# board.net
KiCad netlist of a schematic drawn in EAGLE
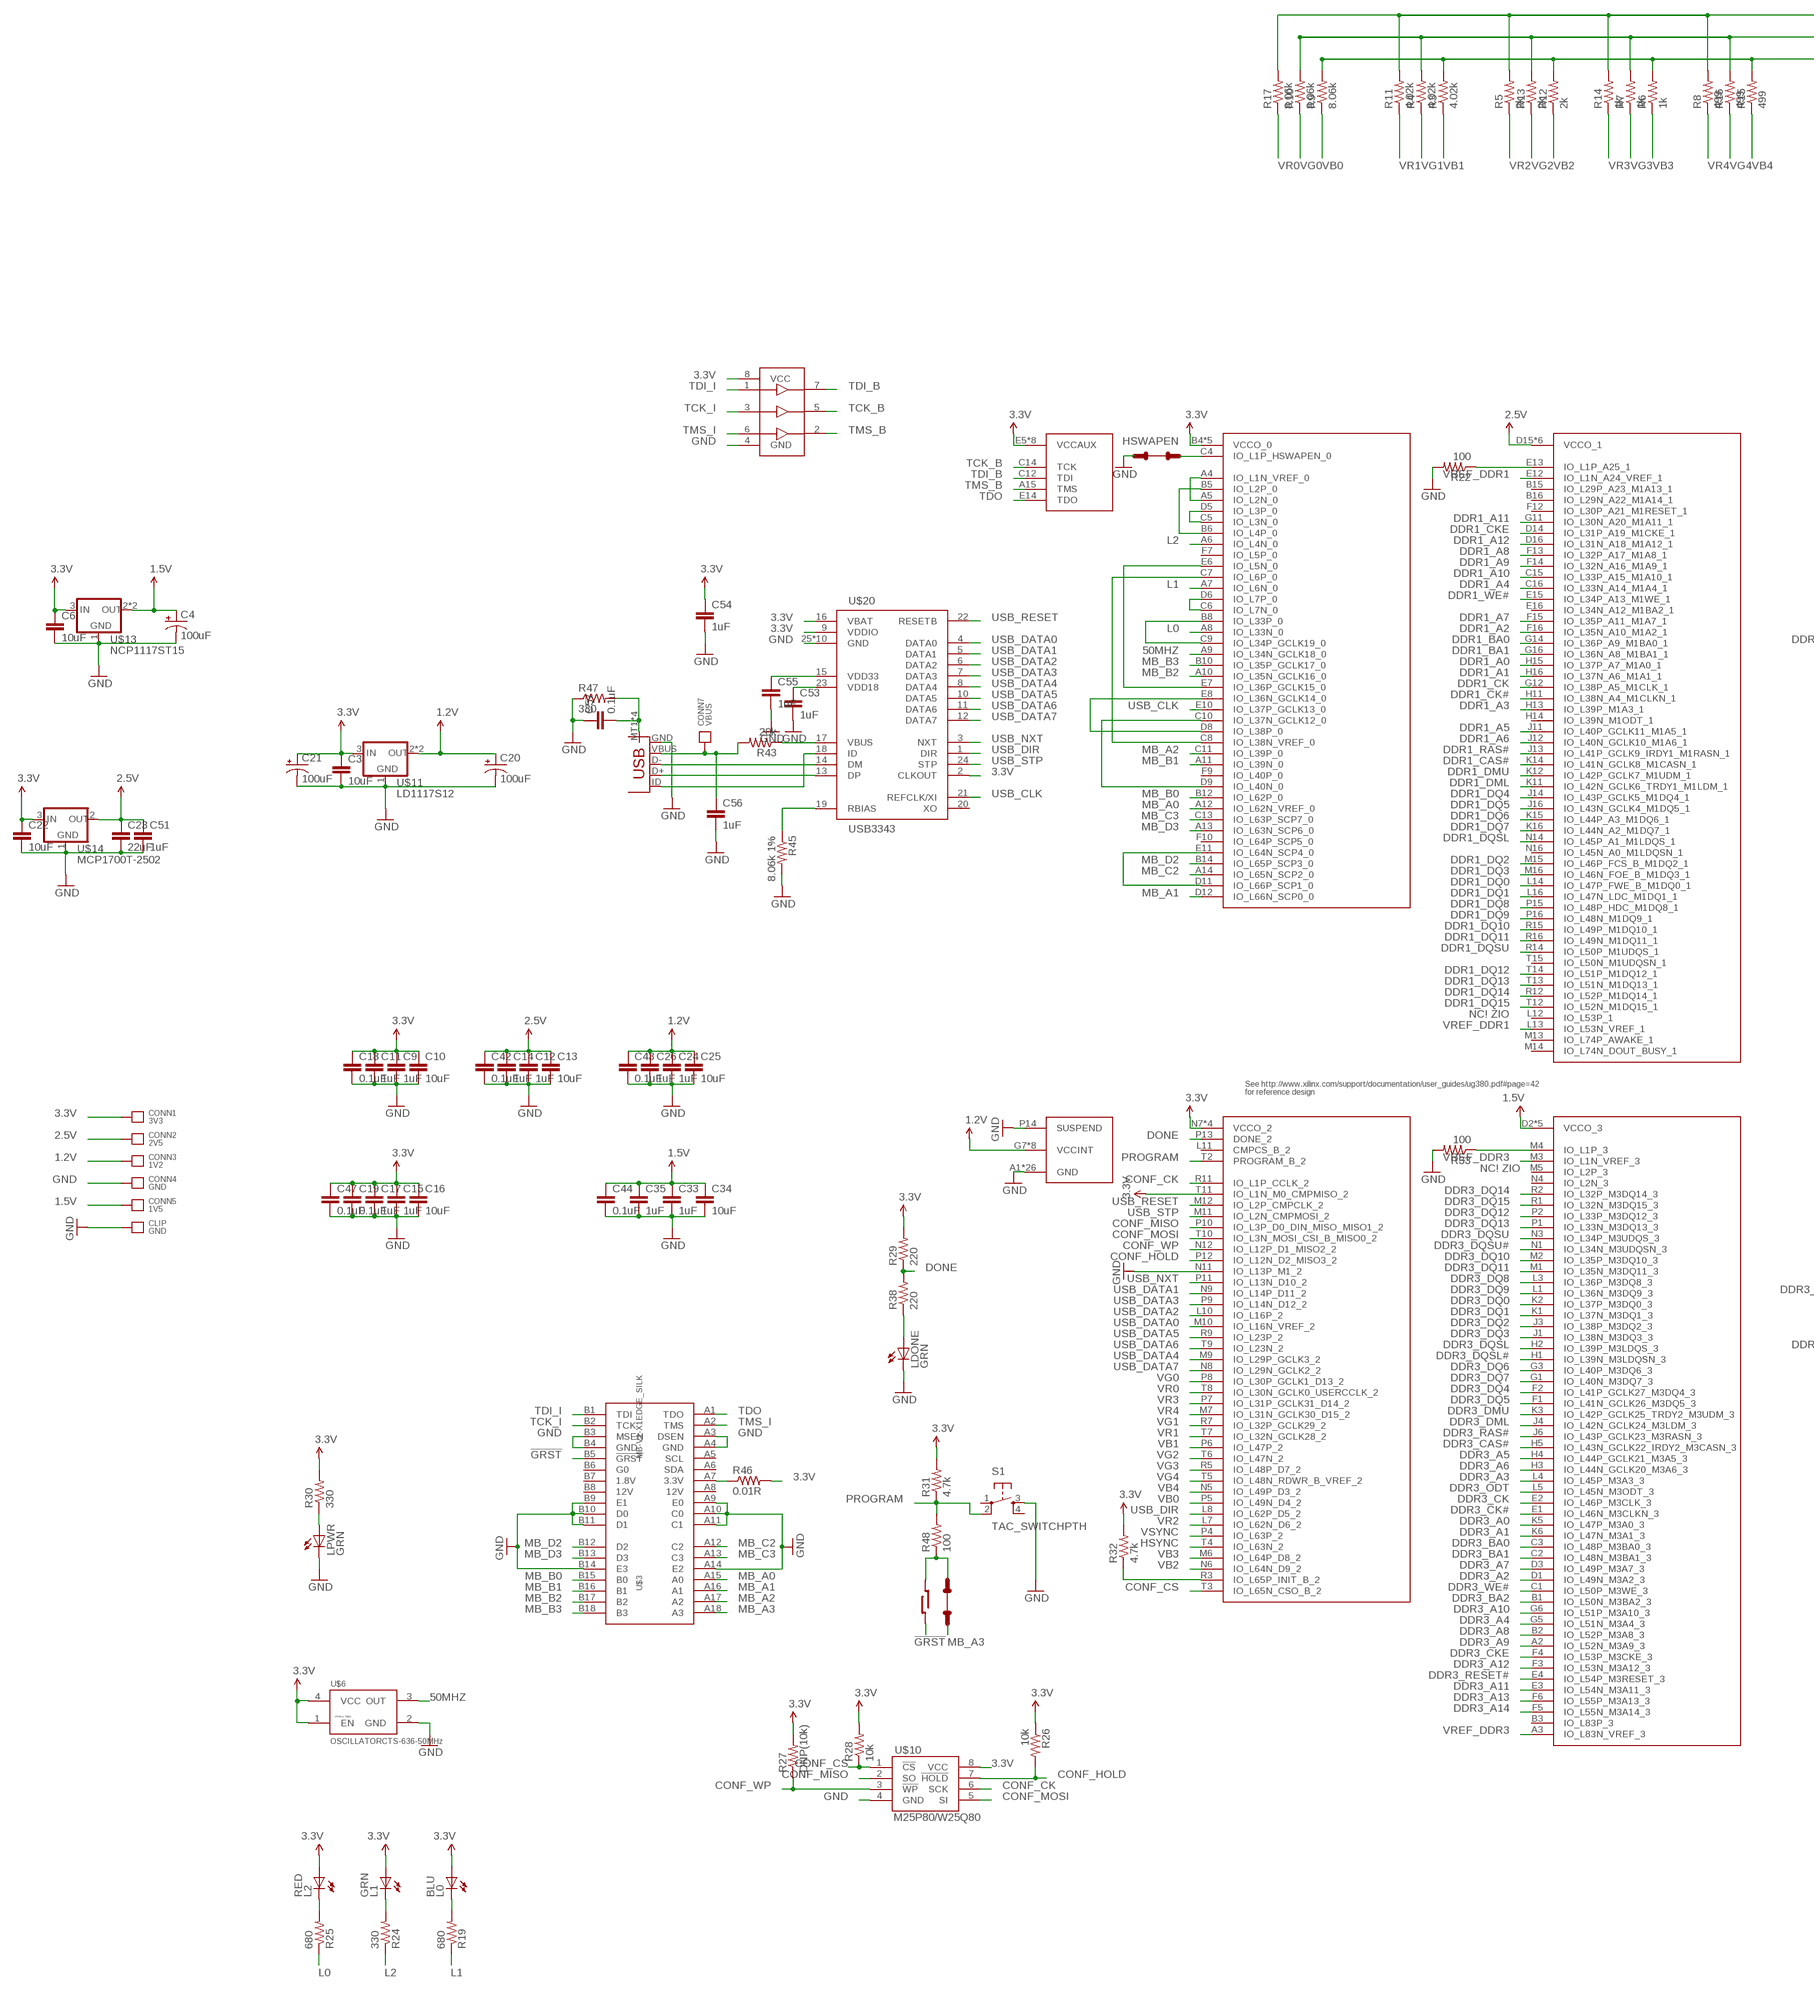
[diagram p0: schematic, sheet 1, part 1 of 2]
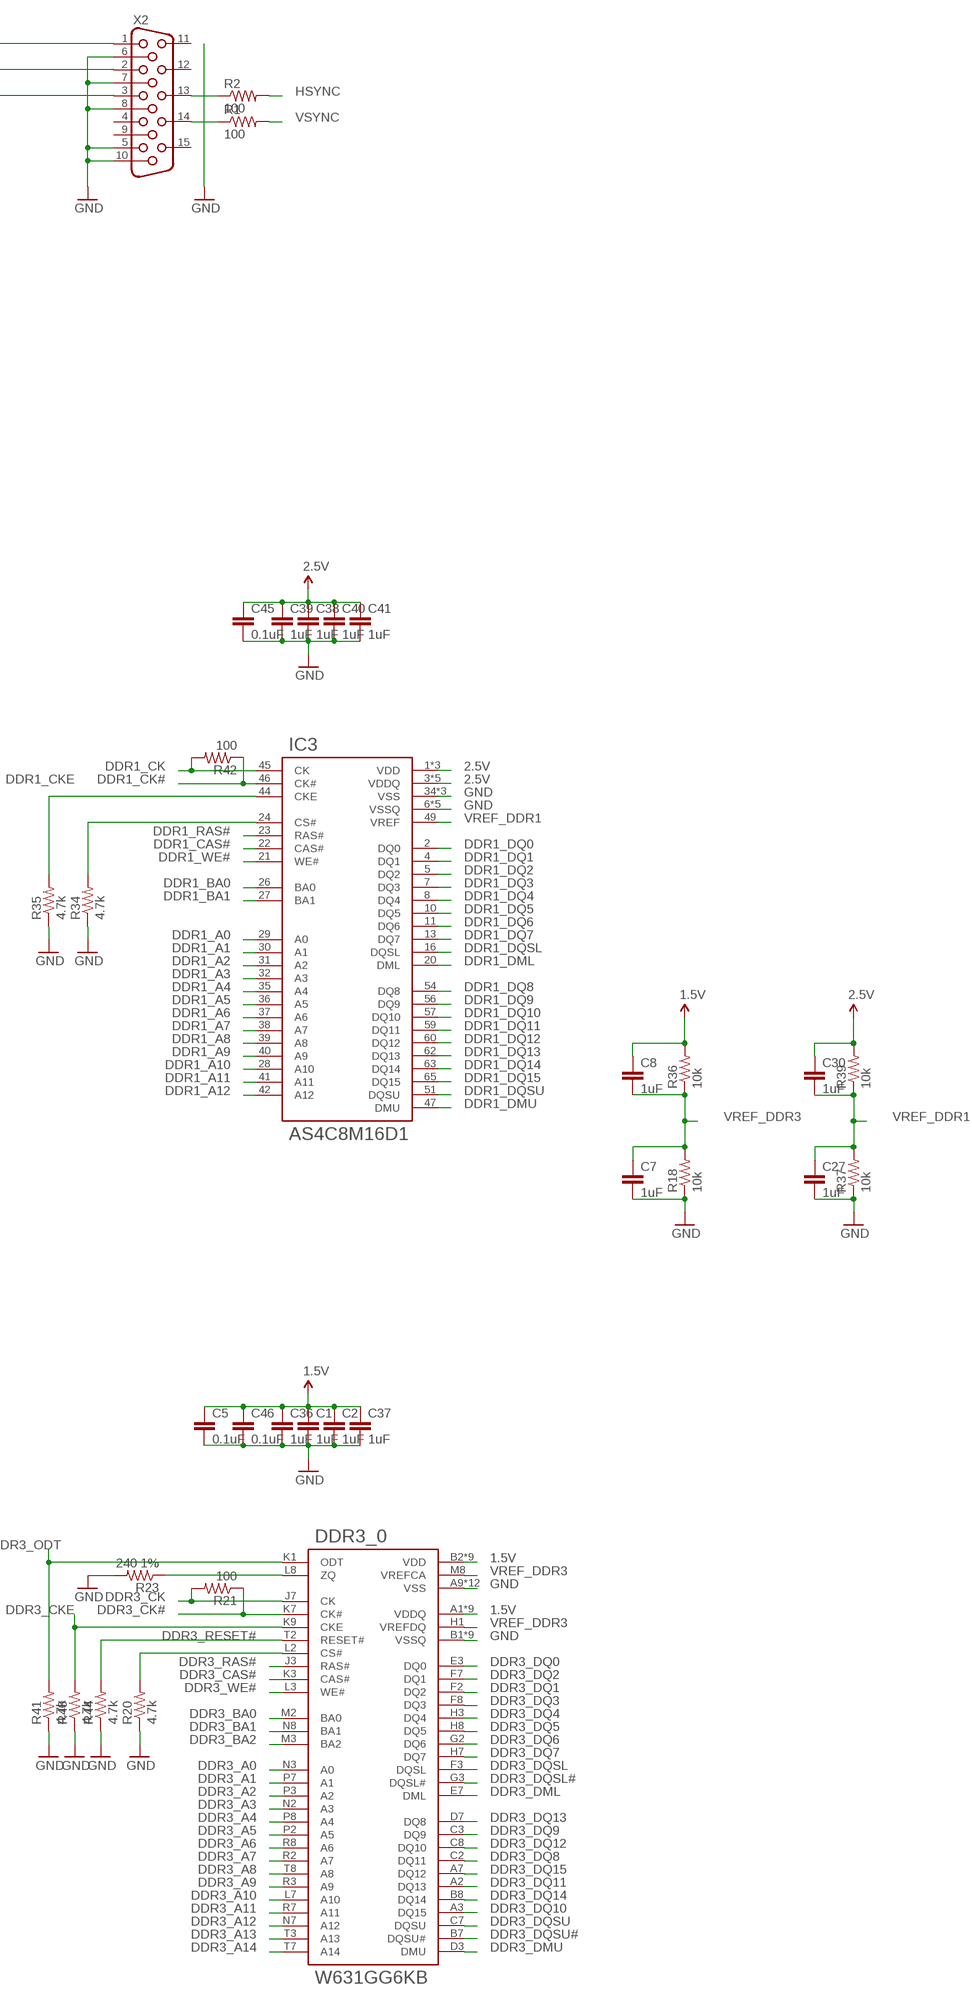
[diagram p1: schematic, sheet 1, part 2 of 2]

(export (version "E")
  (design (tool "Eeschema 10.0.6"))
  (components
    (comp (ref "C1")
      (value "1uF")
      (footprint "eagle-import:0402-CAP")
      (libsource (lib "eagle-import") (part "CAP0402-CAP"))
    )
    (comp (ref "C2")
      (value "1uF")
      (footprint "eagle-import:0402-CAP")
      (libsource (lib "eagle-import") (part "CAP0402-CAP"))
    )
    (comp (ref "C3")
      (value "10uF")
      (footprint "eagle-import:0603-CAP")
      (libsource (lib "eagle-import") (part "CAP0603"))
    )
    (comp (ref "C4")
      (value "100uF")
      (footprint "eagle-import:CAP-5-2")
      (libsource (lib "eagle-import") (part "CAP_POLPTH-5-2"))
    )
    (comp (ref "C5")
      (value "0.1uF")
      (footprint "eagle-import:C0201")
      (libsource (lib "eagle-import") (part "CAP0201"))
    )
    (comp (ref "C6")
      (value "10uF")
      (footprint "eagle-import:0603-CAP")
      (libsource (lib "eagle-import") (part "CAP0603"))
    )
    (comp (ref "C7")
      (value "1uF")
      (footprint "eagle-import:0402-CAP")
      (libsource (lib "eagle-import") (part "CAP0402-CAP"))
    )
    (comp (ref "C8")
      (value "1uF")
      (footprint "eagle-import:0402-CAP")
      (libsource (lib "eagle-import") (part "CAP0402-CAP"))
    )
    (comp (ref "C9")
      (value "1uF")
      (footprint "eagle-import:0402-CAP")
      (libsource (lib "eagle-import") (part "CAP0402-CAP"))
    )
    (comp (ref "C10")
      (value "10uF")
      (footprint "eagle-import:0603-CAP")
      (libsource (lib "eagle-import") (part "CAP0603"))
    )
    (comp (ref "C11")
      (value "1uF")
      (footprint "eagle-import:0402-CAP")
      (libsource (lib "eagle-import") (part "CAP0402-CAP"))
    )
    (comp (ref "C12")
      (value "1uF")
      (footprint "eagle-import:0402-CAP")
      (libsource (lib "eagle-import") (part "CAP0402-CAP"))
    )
    (comp (ref "C13")
      (value "10uF")
      (footprint "eagle-import:0603-CAP")
      (libsource (lib "eagle-import") (part "CAP0603"))
    )
    (comp (ref "C14")
      (value "1uF")
      (footprint "eagle-import:0402-CAP")
      (libsource (lib "eagle-import") (part "CAP0402-CAP"))
    )
    (comp (ref "C15")
      (value "1uF")
      (footprint "eagle-import:0402-CAP")
      (libsource (lib "eagle-import") (part "CAP0402-CAP"))
    )
    (comp (ref "C16")
      (value "10uF")
      (footprint "eagle-import:0603-CAP")
      (libsource (lib "eagle-import") (part "CAP0603"))
    )
    (comp (ref "C17")
      (value "1uF")
      (footprint "eagle-import:0402-CAP")
      (libsource (lib "eagle-import") (part "CAP0402-CAP"))
    )
    (comp (ref "C18")
      (value "0.1uF")
      (footprint "eagle-import:C0201")
      (libsource (lib "eagle-import") (part "CAP0201"))
    )
    (comp (ref "C19")
      (value "0.1uF")
      (footprint "eagle-import:C0201")
      (libsource (lib "eagle-import") (part "CAP0201"))
    )
    (comp (ref "C20")
      (value "100uF")
      (footprint "eagle-import:CAP-5-2")
      (libsource (lib "eagle-import") (part "CAP_POLPTH-5-2"))
    )
    (comp (ref "C21")
      (value "100uF")
      (footprint "eagle-import:CAP-5-2")
      (libsource (lib "eagle-import") (part "CAP_POLPTH-5-2"))
    )
    (comp (ref "C22")
      (value "10uF")
      (footprint "eagle-import:0603-CAP")
      (libsource (lib "eagle-import") (part "CAP0603"))
    )
    (comp (ref "C23")
      (value "22uF")
      (footprint "eagle-import:0805")
      (libsource (lib "eagle-import") (part "CAP0805"))
    )
    (comp (ref "C24")
      (value "1uF")
      (footprint "eagle-import:0402-CAP")
      (libsource (lib "eagle-import") (part "CAP0402-CAP"))
    )
    (comp (ref "C25")
      (value "10uF")
      (footprint "eagle-import:0603-CAP")
      (libsource (lib "eagle-import") (part "CAP0603"))
    )
    (comp (ref "C26")
      (value "1uF")
      (footprint "eagle-import:0402-CAP")
      (libsource (lib "eagle-import") (part "CAP0402-CAP"))
    )
    (comp (ref "C27")
      (value "1uF")
      (footprint "eagle-import:0402-CAP")
      (libsource (lib "eagle-import") (part "CAP0402-CAP"))
    )
    (comp (ref "C30")
      (value "1uF")
      (footprint "eagle-import:0402-CAP")
      (libsource (lib "eagle-import") (part "CAP0402-CAP"))
    )
    (comp (ref "C33")
      (value "1uF")
      (footprint "eagle-import:0402-CAP")
      (libsource (lib "eagle-import") (part "CAP0402-CAP"))
    )
    (comp (ref "C34")
      (value "10uF")
      (footprint "eagle-import:0603-CAP")
      (libsource (lib "eagle-import") (part "CAP0603"))
    )
    (comp (ref "C35")
      (value "1uF")
      (footprint "eagle-import:0402-CAP")
      (libsource (lib "eagle-import") (part "CAP0402-CAP"))
    )
    (comp (ref "C36")
      (value "1uF")
      (footprint "eagle-import:0402-CAP")
      (libsource (lib "eagle-import") (part "CAP0402-CAP"))
    )
    (comp (ref "C37")
      (value "1uF")
      (footprint "eagle-import:0402-CAP")
      (libsource (lib "eagle-import") (part "CAP0402-CAP"))
    )
    (comp (ref "C38")
      (value "1uF")
      (footprint "eagle-import:0402-CAP")
      (libsource (lib "eagle-import") (part "CAP0402-CAP"))
    )
    (comp (ref "C39")
      (value "1uF")
      (footprint "eagle-import:0402-CAP")
      (libsource (lib "eagle-import") (part "CAP0402-CAP"))
    )
    (comp (ref "C40")
      (value "1uF")
      (footprint "eagle-import:0402-CAP")
      (libsource (lib "eagle-import") (part "CAP0402-CAP"))
    )
    (comp (ref "C41")
      (value "1uF")
      (footprint "eagle-import:0402-CAP")
      (libsource (lib "eagle-import") (part "CAP0402-CAP"))
    )
    (comp (ref "C42")
      (value "0.1uF")
      (footprint "eagle-import:C0201")
      (libsource (lib "eagle-import") (part "CAP0201"))
    )
    (comp (ref "C43")
      (value "0.1uF")
      (footprint "eagle-import:C0201")
      (libsource (lib "eagle-import") (part "CAP0201"))
    )
    (comp (ref "C44")
      (value "0.1uF")
      (footprint "eagle-import:C0201")
      (libsource (lib "eagle-import") (part "CAP0201"))
    )
    (comp (ref "C45")
      (value "0.1uF")
      (footprint "eagle-import:C0201")
      (libsource (lib "eagle-import") (part "CAP0201"))
    )
    (comp (ref "C46")
      (value "0.1uF")
      (footprint "eagle-import:C0201")
      (libsource (lib "eagle-import") (part "CAP0201"))
    )
    (comp (ref "C47")
      (value "0.1uF")
      (footprint "eagle-import:C0201")
      (libsource (lib "eagle-import") (part "CAP0201"))
    )
    (comp (ref "C51")
      (value "1uF")
      (footprint "eagle-import:0402-CAP")
      (libsource (lib "eagle-import") (part "CAP0402-CAP"))
    )
    (comp (ref "C53")
      (value "1uF")
      (footprint "eagle-import:0402-CAP")
      (libsource (lib "eagle-import") (part "CAP0402-CAP"))
    )
    (comp (ref "C54")
      (value "1uF")
      (footprint "eagle-import:0402-CAP")
      (libsource (lib "eagle-import") (part "CAP0402-CAP"))
    )
    (comp (ref "C55")
      (value "1uF")
      (footprint "eagle-import:0402-CAP")
      (libsource (lib "eagle-import") (part "CAP0402-CAP"))
    )
    (comp (ref "C56")
      (value "1uF")
      (footprint "eagle-import:0402-CAP")
      (libsource (lib "eagle-import") (part "CAP0402-CAP"))
    )
    (comp (ref "C57")
      (value "0.1uF")
      (footprint "eagle-import:0402-CAP")
      (libsource (lib "eagle-import") (part "CAP0402-CAP"))
    )
    (comp (ref "CLIP")
      (value "GND")
      (footprint "eagle-import:CLIP-AREA")
      (libsource (lib "eagle-import") (part "CONNECTORCLIP"))
    )
    (comp (ref "CONN1")
      (value "3V3")
      (footprint "eagle-import:HOLE_22AWG")
      (libsource (lib "eagle-import") (part "CONNECTOR22AWG"))
    )
    (comp (ref "CONN2")
      (value "2V5")
      (footprint "eagle-import:HOLE_22AWG")
      (libsource (lib "eagle-import") (part "CONNECTOR22AWG"))
    )
    (comp (ref "CONN3")
      (value "1V2")
      (footprint "eagle-import:HOLE_22AWG")
      (libsource (lib "eagle-import") (part "CONNECTOR22AWG"))
    )
    (comp (ref "CONN4")
      (value "GND")
      (footprint "eagle-import:HOLE_22AWG")
      (libsource (lib "eagle-import") (part "CONNECTOR22AWG"))
    )
    (comp (ref "CONN5")
      (value "1V5")
      (footprint "eagle-import:HOLE_22AWG")
      (libsource (lib "eagle-import") (part "CONNECTOR22AWG"))
    )
    (comp (ref "CONN7")
      (value "VBUS")
      (footprint "eagle-import:HOLE_22AWG")
      (libsource (lib "eagle-import") (part "CONNECTOR22AWG"))
    )
    (comp (ref "DDR3_0")
      (value "W631GG6KB")
      (footprint "eagle-import:BGA96")
      (libsource (lib "eagle-import") (part "DDR3X16"))
    )
    (comp (ref "IC1")
      (value "XC6S{9,16,25}LX-FT256")
      (footprint "eagle-import:XILINX_FT256")
      (libsource (lib "eagle-import") (part "XC6S{9,16,25}LX-FT256"))
    )
    (comp (ref "IC2")
      (value "74LVC3G34")
      (footprint "eagle-import:TSSOP8")
      (libsource (lib "eagle-import") (part "74X3G34"))
    )
    (comp (ref "IC3")
      (value "AS4C8M16D1")
      (footprint "eagle-import:TSOP66-400")
      (libsource (lib "eagle-import") (part "DDR1X16"))
    )
    (comp (ref "JP1")
      (value "USBMICRO")
      (footprint "eagle-import:USB-MICRO")
      (libsource (lib "eagle-import") (part "USBMICRO"))
    )
    (comp (ref "L0")
      (value "BLU")
      (footprint "eagle-import:0603_LED")
      (libsource (lib "eagle-import") (part "LED0603"))
    )
    (comp (ref "L1")
      (value "GRN")
      (footprint "eagle-import:0603_LED")
      (libsource (lib "eagle-import") (part "LED0603"))
    )
    (comp (ref "L2")
      (value "RED")
      (footprint "eagle-import:0603_LED")
      (libsource (lib "eagle-import") (part "LED0603"))
    )
    (comp (ref "LDONE")
      (value "GRN")
      (footprint "eagle-import:0603_LED")
      (libsource (lib "eagle-import") (part "LED0603"))
    )
    (comp (ref "LPWR")
      (value "GRN")
      (footprint "eagle-import:0603_LED")
      (libsource (lib "eagle-import") (part "LED0603"))
    )
    (comp (ref "R1")
      (value "100")
      (footprint "eagle-import:0603-RES")
      (libsource (lib "eagle-import") (part "RESISTOR0603"))
    )
    (comp (ref "R2")
      (value "100")
      (footprint "eagle-import:0603-RES")
      (libsource (lib "eagle-import") (part "RESISTOR0603"))
    )
    (comp (ref "R3")
      (value "4.02k")
      (footprint "eagle-import:0603-RES")
      (libsource (lib "eagle-import") (part "RESISTOR0603"))
    )
    (comp (ref "R4")
      (value "4.02k")
      (footprint "eagle-import:0603-RES")
      (libsource (lib "eagle-import") (part "RESISTOR0603"))
    )
    (comp (ref "R5")
      (value "2k")
      (footprint "eagle-import:0603-RES")
      (libsource (lib "eagle-import") (part "RESISTOR0603"))
    )
    (comp (ref "R6")
      (value "1k")
      (footprint "eagle-import:0603-RES")
      (libsource (lib "eagle-import") (part "RESISTOR0603"))
    )
    (comp (ref "R7")
      (value "1k")
      (footprint "eagle-import:0603-RES")
      (libsource (lib "eagle-import") (part "RESISTOR0603"))
    )
    (comp (ref "R8")
      (value "499")
      (footprint "eagle-import:0603-RES")
      (libsource (lib "eagle-import") (part "RESISTOR0603"))
    )
    (comp (ref "R9")
      (value "8.06k")
      (footprint "eagle-import:0603-RES")
      (libsource (lib "eagle-import") (part "RESISTOR0603"))
    )
    (comp (ref "R10")
      (value "8.06k")
      (footprint "eagle-import:0603-RES")
      (libsource (lib "eagle-import") (part "RESISTOR0603"))
    )
    (comp (ref "R11")
      (value "4.02k")
      (footprint "eagle-import:0603-RES")
      (libsource (lib "eagle-import") (part "RESISTOR0603"))
    )
    (comp (ref "R12")
      (value "2k")
      (footprint "eagle-import:0603-RES")
      (libsource (lib "eagle-import") (part "RESISTOR0603"))
    )
    (comp (ref "R13")
      (value "2k")
      (footprint "eagle-import:0603-RES")
      (libsource (lib "eagle-import") (part "RESISTOR0603"))
    )
    (comp (ref "R14")
      (value "1k")
      (footprint "eagle-import:0603-RES")
      (libsource (lib "eagle-import") (part "RESISTOR0603"))
    )
    (comp (ref "R15")
      (value "499")
      (footprint "eagle-import:0603-RES")
      (libsource (lib "eagle-import") (part "RESISTOR0603"))
    )
    (comp (ref "R16")
      (value "499")
      (footprint "eagle-import:0603-RES")
      (libsource (lib "eagle-import") (part "RESISTOR0603"))
    )
    (comp (ref "R17")
      (value "8.06k")
      (footprint "eagle-import:0603-RES")
      (libsource (lib "eagle-import") (part "RESISTOR0603"))
    )
    (comp (ref "R18")
      (value "10k")
      (footprint "eagle-import:0603-RES")
      (libsource (lib "eagle-import") (part "RESISTOR0603"))
    )
    (comp (ref "R19")
      (value "680")
      (footprint "eagle-import:0603-RES")
      (libsource (lib "eagle-import") (part "RESISTOR0603"))
    )
    (comp (ref "R20")
      (value "4.7k")
      (footprint "eagle-import:0402-RES")
      (libsource (lib "eagle-import") (part "RESISTOR0402"))
    )
    (comp (ref "R21")
      (value "100")
      (footprint "eagle-import:0603-RES")
      (libsource (lib "eagle-import") (part "RESISTOR0603"))
    )
    (comp (ref "R22")
      (value "100")
      (footprint "eagle-import:0603-RES")
      (libsource (lib "eagle-import") (part "RESISTOR0603"))
    )
    (comp (ref "R23")
      (value "240 1%")
      (footprint "eagle-import:0402-RES")
      (libsource (lib "eagle-import") (part "RESISTOR0402"))
    )
    (comp (ref "R24")
      (value "330")
      (footprint "eagle-import:0603-RES")
      (libsource (lib "eagle-import") (part "RESISTOR0603"))
    )
    (comp (ref "R25")
      (value "680")
      (footprint "eagle-import:0603-RES")
      (libsource (lib "eagle-import") (part "RESISTOR0603"))
    )
    (comp (ref "R26")
      (value "10k")
      (footprint "eagle-import:0402-RES")
      (libsource (lib "eagle-import") (part "RESISTOR0402"))
    )
    (comp (ref "R27")
      (value "DNP(10k)")
      (footprint "eagle-import:0402-RES")
      (libsource (lib "eagle-import") (part "RESISTOR0402"))
    )
    (comp (ref "R28")
      (value "10k")
      (footprint "eagle-import:0603-RES")
      (libsource (lib "eagle-import") (part "RESISTOR0603"))
    )
    (comp (ref "R29")
      (value "220")
      (footprint "eagle-import:0603-RES")
      (libsource (lib "eagle-import") (part "RESISTOR0603"))
    )
    (comp (ref "R30")
      (value "330")
      (footprint "eagle-import:0603-RES")
      (libsource (lib "eagle-import") (part "RESISTOR0603"))
    )
    (comp (ref "R31")
      (value "4.7k")
      (footprint "eagle-import:0603-RES")
      (libsource (lib "eagle-import") (part "RESISTOR0603"))
    )
    (comp (ref "R32")
      (value "4.7k")
      (footprint "eagle-import:0603-RES")
      (libsource (lib "eagle-import") (part "RESISTOR0603"))
    )
    (comp (ref "R33")
      (value "100")
      (footprint "eagle-import:0603-RES")
      (libsource (lib "eagle-import") (part "RESISTOR0603"))
    )
    (comp (ref "R34")
      (value "4.7k")
      (footprint "eagle-import:0402-RES")
      (libsource (lib "eagle-import") (part "RESISTOR0402"))
    )
    (comp (ref "R35")
      (value "4.7k")
      (footprint "eagle-import:0402-RES")
      (libsource (lib "eagle-import") (part "RESISTOR0402"))
    )
    (comp (ref "R36")
      (value "10k")
      (footprint "eagle-import:0603-RES")
      (libsource (lib "eagle-import") (part "RESISTOR0603"))
    )
    (comp (ref "R37")
      (value "10k")
      (footprint "eagle-import:0603-RES")
      (libsource (lib "eagle-import") (part "RESISTOR0603"))
    )
    (comp (ref "R38")
      (value "220")
      (footprint "eagle-import:0603-RES")
      (libsource (lib "eagle-import") (part "RESISTOR0603"))
    )
    (comp (ref "R39")
      (value "10k")
      (footprint "eagle-import:0603-RES")
      (libsource (lib "eagle-import") (part "RESISTOR0603"))
    )
    (comp (ref "R40")
      (value "4.7k")
      (footprint "eagle-import:0402-RES")
      (libsource (lib "eagle-import") (part "RESISTOR0402"))
    )
    (comp (ref "R41")
      (value "4.7k")
      (footprint "eagle-import:0402-RES")
      (libsource (lib "eagle-import") (part "RESISTOR0402"))
    )
    (comp (ref "R42")
      (value "100")
      (footprint "eagle-import:0402-RES")
      (libsource (lib "eagle-import") (part "RESISTOR0402"))
    )
    (comp (ref "R43")
      (value "20k")
      (footprint "eagle-import:0402-RES")
      (libsource (lib "eagle-import") (part "RESISTOR0402"))
    )
    (comp (ref "R44")
      (value "4.7k")
      (footprint "eagle-import:0402-RES")
      (libsource (lib "eagle-import") (part "RESISTOR0402"))
    )
    (comp (ref "R45")
      (value "8.06k 1%")
      (footprint "eagle-import:0603-RES")
      (libsource (lib "eagle-import") (part "RESISTOR0603"))
    )
    (comp (ref "R46")
      (value "0.01R")
      (footprint "eagle-import:0603-RES")
      (libsource (lib "eagle-import") (part "RESISTOR0603"))
    )
    (comp (ref "R47")
      (value "330")
      (footprint "eagle-import:0603-RES")
      (libsource (lib "eagle-import") (part "RESISTOR0603"))
    )
    (comp (ref "R48")
      (value "100")
      (footprint "eagle-import:0603-RES")
      (libsource (lib "eagle-import") (part "RESISTOR0603"))
    )
    (comp (ref "S1")
      (value "TAC_SWITCHPTH")
      (footprint "eagle-import:TACTILE-PTH")
      (libsource (lib "eagle-import") (part "TAC_SWITCHPTH"))
    )
    (comp (ref "SB1")
      (value "SOLDER-BRIDGEOPEN")
      (footprint "eagle-import:SOLDER-BRIDGE-OPEN")
      (libsource (lib "eagle-import") (part "SOLDER-BRIDGEOPEN"))
    )
    (comp (ref "SB2")
      (value "TRACE-CUT")
      (footprint "eagle-import:TRACE-CUT")
      (libsource (lib "eagle-import") (part "TRACE-CUT"))
    )
    (comp (ref "SB5")
      (value "TRACE-CUT")
      (footprint "eagle-import:TRACE-CUT")
      (libsource (lib "eagle-import") (part "TRACE-CUT"))
    )
    (comp (ref "U$3")
      (value "MB-V1-X1EDGE_SILK")
      (footprint "eagle-import:MB-V1-X1-EDGE")
      (libsource (lib "eagle-import") (part "MB-V1-X1EDGE_SILK"))
    )
    (comp (ref "U$6")
      (value "OSCILLATORCTS-636-50MHz")
      (footprint "eagle-import:CTS-636")
      (libsource (lib "eagle-import") (part "OSCILLATORCTS-636"))
    )
    (comp (ref "U$10")
      (value "M25P80/W25Q80")
      (footprint "eagle-import:SO08")
      (libsource (lib "eagle-import") (part "S25FL"))
    )
    (comp (ref "U$11")
      (value "LD1117S12")
      (footprint "eagle-import:SOT223")
      (libsource (lib "eagle-import") (part "VREGSOT223"))
    )
    (comp (ref "U$13")
      (value "NCP1117ST15")
      (footprint "eagle-import:SOT223")
      (libsource (lib "eagle-import") (part "VREGSOT223"))
    )
    (comp (ref "U$14")
      (value "MCP1700T-2502")
      (footprint "eagle-import:SOT23-3")
      (libsource (lib "eagle-import") (part "VREGSOT23-3"))
    )
    (comp (ref "U$20")
      (value "USB3343")
      (footprint "eagle-import:QFN24")
      (libsource (lib "eagle-import") (part "USB3343"))
    )
    (comp (ref "X2")
      (value "HF15H")
      (footprint "eagle-import:HDF15H")
      (libsource (lib "eagle-import") (part "HF15H"))
    )
  )
  (nets
    (net (code "1") (name "/50MHZ") (class "Default")
      (node (ref "IC1") (pin "A9") (pinfunction "IO_L34N_GCLK18_0_A9") (pintype "bidirectional"))
      (node (ref "U$6") (pin "3") (pinfunction "OUT_3") (pintype "bidirectional"))
    )
    (net (code "2") (name "/CONF_CK") (class "Default")
      (node (ref "IC1") (pin "R11") (pinfunction "IO_L1P_CCLK_2_R11") (pintype "bidirectional"))
      (node (ref "U$10") (pin "6") (pinfunction "SCK_6") (pintype "bidirectional"))
    )
    (net (code "3") (name "/CONF_CS") (class "Default")
      (node (ref "IC1") (pin "T3") (pinfunction "IO_L65N_CSO_B_2_T3") (pintype "bidirectional"))
      (node (ref "R28") (pin "1") (pinfunction "1_1") (pintype "passive"))
      (node (ref "U$10") (pin "1") (pinfunction "~{CS}_1") (pintype "bidirectional"))
    )
    (net (code "4") (name "/CONF_HOLD") (class "Default")
      (node (ref "IC1") (pin "P12") (pinfunction "IO_L12N_D2_MISO3_2_P12") (pintype "bidirectional"))
      (node (ref "R26") (pin "2") (pinfunction "2_2") (pintype "passive"))
      (node (ref "U$10") (pin "7") (pinfunction "~{HOLD}_7") (pintype "bidirectional"))
    )
    (net (code "5") (name "/CONF_MISO") (class "Default")
      (node (ref "IC1") (pin "P10") (pinfunction "IO_L3P_D0_DIN_MISO_MISO1_2_P10") (pintype "bidirectional"))
      (node (ref "U$10") (pin "2") (pinfunction "SO_2") (pintype "bidirectional"))
    )
    (net (code "6") (name "/CONF_MOSI") (class "Default")
      (node (ref "IC1") (pin "T10") (pinfunction "IO_L3N_MOSI_CSI_B_MISO0_2_T10") (pintype "bidirectional"))
      (node (ref "U$10") (pin "5") (pinfunction "SI_5") (pintype "bidirectional"))
    )
    (net (code "7") (name "/CONF_WP") (class "Default")
      (node (ref "IC1") (pin "N12") (pinfunction "IO_L12P_D1_MISO2_2_N12") (pintype "bidirectional"))
      (node (ref "R27") (pin "1") (pinfunction "1_1") (pintype "passive"))
      (node (ref "U$10") (pin "3") (pinfunction "~{WP}_3") (pintype "bidirectional"))
    )
    (net (code "8") (name "/DDR1_A0") (class "Default")
      (node (ref "IC1") (pin "H15") (pinfunction "IO_L37P_A7_M1A0_1_H15") (pintype "bidirectional"))
      (node (ref "IC3") (pin "29") (pinfunction "A0_29") (pintype "input"))
    )
    (net (code "9") (name "/DDR1_A1") (class "Default")
      (node (ref "IC1") (pin "H16") (pinfunction "IO_L37N_A6_M1A1_1_H16") (pintype "bidirectional"))
      (node (ref "IC3") (pin "30") (pinfunction "A1_30") (pintype "input"))
    )
    (net (code "10") (name "/DDR1_A2") (class "Default")
      (node (ref "IC1") (pin "F16") (pinfunction "IO_L35N_A10_M1A2_1_F16") (pintype "bidirectional"))
      (node (ref "IC3") (pin "31") (pinfunction "A2_31") (pintype "input"))
    )
    (net (code "11") (name "/DDR1_A3") (class "Default")
      (node (ref "IC1") (pin "H13") (pinfunction "IO_L39P_M1A3_1_H13") (pintype "bidirectional"))
      (node (ref "IC3") (pin "32") (pinfunction "A3_32") (pintype "input"))
    )
    (net (code "12") (name "/DDR1_A4") (class "Default")
      (node (ref "IC1") (pin "C16") (pinfunction "IO_L33N_A14_M1A4_1_C16") (pintype "bidirectional"))
      (node (ref "IC3") (pin "35") (pinfunction "A4_35") (pintype "input"))
    )
    (net (code "13") (name "/DDR1_A5") (class "Default")
      (node (ref "IC1") (pin "J11") (pinfunction "IO_L40P_GCLK11_M1A5_1_J11") (pintype "bidirectional"))
      (node (ref "IC3") (pin "36") (pinfunction "A5_36") (pintype "input"))
    )
    (net (code "14") (name "/DDR1_A6") (class "Default")
      (node (ref "IC1") (pin "J12") (pinfunction "IO_L40N_GCLK10_M1A6_1_J12") (pintype "bidirectional"))
      (node (ref "IC3") (pin "37") (pinfunction "A6_37") (pintype "input"))
    )
    (net (code "15") (name "/DDR1_A7") (class "Default")
      (node (ref "IC1") (pin "F15") (pinfunction "IO_L35P_A11_M1A7_1_F15") (pintype "bidirectional"))
      (node (ref "IC3") (pin "38") (pinfunction "A7_38") (pintype "input"))
    )
    (net (code "16") (name "/DDR1_A8") (class "Default")
      (node (ref "IC1") (pin "F13") (pinfunction "IO_L32P_A17_M1A8_1_F13") (pintype "bidirectional"))
      (node (ref "IC3") (pin "39") (pinfunction "A8_39") (pintype "input"))
    )
    (net (code "17") (name "/DDR1_A9") (class "Default")
      (node (ref "IC1") (pin "F14") (pinfunction "IO_L32N_A16_M1A9_1_F14") (pintype "bidirectional"))
      (node (ref "IC3") (pin "40") (pinfunction "A9_40") (pintype "input"))
    )
    (net (code "18") (name "/DDR1_A10") (class "Default")
      (node (ref "IC1") (pin "C15") (pinfunction "IO_L33P_A15_M1A10_1_C15") (pintype "bidirectional"))
      (node (ref "IC3") (pin "28") (pinfunction "A10_28") (pintype "input"))
    )
    (net (code "19") (name "/DDR1_A11") (class "Default")
      (node (ref "IC1") (pin "G11") (pinfunction "IO_L30N_A20_M1A11_1_G11") (pintype "bidirectional"))
      (node (ref "IC3") (pin "41") (pinfunction "A11_41") (pintype "input"))
    )
    (net (code "20") (name "/DDR1_A12") (class "Default")
      (node (ref "IC1") (pin "D16") (pinfunction "IO_L31N_A18_M1A12_1_D16") (pintype "bidirectional"))
      (node (ref "IC3") (pin "42") (pinfunction "A12_42") (pintype "input"))
    )
    (net (code "21") (name "/DDR1_BA0") (class "Default")
      (node (ref "IC1") (pin "G14") (pinfunction "IO_L36P_A9_M1BA0_1_G14") (pintype "bidirectional"))
      (node (ref "IC3") (pin "26") (pinfunction "BA0_26") (pintype "input"))
    )
    (net (code "22") (name "/DDR1_BA1") (class "Default")
      (node (ref "IC1") (pin "G16") (pinfunction "IO_L36N_A8_M1BA1_1_G16") (pintype "bidirectional"))
      (node (ref "IC3") (pin "27") (pinfunction "BA1_27") (pintype "input"))
    )
    (net (code "23") (name "/DDR1_CAS#") (class "Default")
      (node (ref "IC1") (pin "K14") (pinfunction "IO_L41N_GCLK8_M1CASN_1_K14") (pintype "bidirectional"))
      (node (ref "IC3") (pin "22") (pinfunction "CAS#_22") (pintype "input"))
    )
    (net (code "24") (name "/DDR1_CK") (class "Default")
      (node (ref "IC1") (pin "G12") (pinfunction "IO_L38P_A5_M1CLK_1_G12") (pintype "bidirectional"))
      (node (ref "IC3") (pin "45") (pinfunction "CK_45") (pintype "input"))
      (node (ref "R42") (pin "2") (pinfunction "2_2") (pintype "passive"))
    )
    (net (code "25") (name "/DDR1_CK#") (class "Default")
      (node (ref "IC1") (pin "H11") (pinfunction "IO_L38N_A4_M1CLKN_1_H11") (pintype "bidirectional"))
      (node (ref "IC3") (pin "46") (pinfunction "CK#_46") (pintype "input"))
      (node (ref "R42") (pin "1") (pinfunction "1_1") (pintype "passive"))
    )
    (net (code "26") (name "/DDR1_CKE") (class "Default")
      (node (ref "IC1") (pin "D14") (pinfunction "IO_L31P_A19_M1CKE_1_D14") (pintype "bidirectional"))
      (node (ref "IC3") (pin "44") (pinfunction "CKE_44") (pintype "input"))
      (node (ref "R35") (pin "2") (pinfunction "2_2") (pintype "passive"))
    )
    (net (code "27") (name "/DDR1_DML") (class "Default")
      (node (ref "IC1") (pin "K11") (pinfunction "IO_L42N_GCLK6_TRDY1_M1LDM_1_K11") (pintype "bidirectional"))
      (node (ref "IC3") (pin "20") (pinfunction "DML_20") (pintype "input"))
    )
    (net (code "28") (name "/DDR1_DMU") (class "Default")
      (node (ref "IC1") (pin "K12") (pinfunction "IO_L42P_GCLK7_M1UDM_1_K12") (pintype "bidirectional"))
      (node (ref "IC3") (pin "47") (pinfunction "DMU_47") (pintype "input"))
    )
    (net (code "29") (name "/DDR1_DQ0") (class "Default")
      (node (ref "IC1") (pin "L14") (pinfunction "IO_L47P_FWE_B_M1DQ0_1_L14") (pintype "bidirectional"))
      (node (ref "IC3") (pin "2") (pinfunction "DQ0_2") (pintype "bidirectional"))
    )
    (net (code "30") (name "/DDR1_DQ1") (class "Default")
      (node (ref "IC1") (pin "L16") (pinfunction "IO_L47N_LDC_M1DQ1_1_L16") (pintype "bidirectional"))
      (node (ref "IC3") (pin "4") (pinfunction "DQ1_4") (pintype "bidirectional"))
    )
    (net (code "31") (name "/DDR1_DQ2") (class "Default")
      (node (ref "IC1") (pin "M15") (pinfunction "IO_L46P_FCS_B_M1DQ2_1_M15") (pintype "bidirectional"))
      (node (ref "IC3") (pin "5") (pinfunction "DQ2_5") (pintype "bidirectional"))
    )
    (net (code "32") (name "/DDR1_DQ3") (class "Default")
      (node (ref "IC1") (pin "M16") (pinfunction "IO_L46N_FOE_B_M1DQ3_1_M16") (pintype "bidirectional"))
      (node (ref "IC3") (pin "7") (pinfunction "DQ3_7") (pintype "bidirectional"))
    )
    (net (code "33") (name "/DDR1_DQ4") (class "Default")
      (node (ref "IC1") (pin "J14") (pinfunction "IO_L43P_GCLK5_M1DQ4_1_J14") (pintype "bidirectional"))
      (node (ref "IC3") (pin "8") (pinfunction "DQ4_8") (pintype "bidirectional"))
    )
    (net (code "34") (name "/DDR1_DQ5") (class "Default")
      (node (ref "IC1") (pin "J16") (pinfunction "IO_L43N_GCLK4_M1DQ5_1_J16") (pintype "bidirectional"))
      (node (ref "IC3") (pin "10") (pinfunction "DQ5_10") (pintype "bidirectional"))
    )
    (net (code "35") (name "/DDR1_DQ6") (class "Default")
      (node (ref "IC1") (pin "K15") (pinfunction "IO_L44P_A3_M1DQ6_1_K15") (pintype "bidirectional"))
      (node (ref "IC3") (pin "11") (pinfunction "DQ6_11") (pintype "bidirectional"))
    )
    (net (code "36") (name "/DDR1_DQ7") (class "Default")
      (node (ref "IC1") (pin "K16") (pinfunction "IO_L44N_A2_M1DQ7_1_K16") (pintype "bidirectional"))
      (node (ref "IC3") (pin "13") (pinfunction "DQ7_13") (pintype "bidirectional"))
    )
    (net (code "37") (name "/DDR1_DQ8") (class "Default")
      (node (ref "IC1") (pin "P15") (pinfunction "IO_L48P_HDC_M1DQ8_1_P15") (pintype "bidirectional"))
      (node (ref "IC3") (pin "54") (pinfunction "DQ8_54") (pintype "bidirectional"))
    )
    (net (code "38") (name "/DDR1_DQ9") (class "Default")
      (node (ref "IC1") (pin "P16") (pinfunction "IO_L48N_M1DQ9_1_P16") (pintype "bidirectional"))
      (node (ref "IC3") (pin "56") (pinfunction "DQ9_56") (pintype "bidirectional"))
    )
    (net (code "39") (name "/DDR1_DQ10") (class "Default")
      (node (ref "IC1") (pin "R15") (pinfunction "IO_L49P_M1DQ10_1_R15") (pintype "bidirectional"))
      (node (ref "IC3") (pin "57") (pinfunction "DQ10_57") (pintype "bidirectional"))
    )
    (net (code "40") (name "/DDR1_DQ11") (class "Default")
      (node (ref "IC1") (pin "R16") (pinfunction "IO_L49N_M1DQ11_1_R16") (pintype "bidirectional"))
      (node (ref "IC3") (pin "59") (pinfunction "DQ11_59") (pintype "bidirectional"))
    )
    (net (code "41") (name "/DDR1_DQ12") (class "Default")
      (node (ref "IC1") (pin "T14") (pinfunction "IO_L51P_M1DQ12_1_T14") (pintype "bidirectional"))
      (node (ref "IC3") (pin "60") (pinfunction "DQ12_60") (pintype "bidirectional"))
    )
    (net (code "42") (name "/DDR1_DQ13") (class "Default")
      (node (ref "IC1") (pin "T13") (pinfunction "IO_L51N_M1DQ13_1_T13") (pintype "bidirectional"))
      (node (ref "IC3") (pin "62") (pinfunction "DQ13_62") (pintype "bidirectional"))
    )
    (net (code "43") (name "/DDR1_DQ14") (class "Default")
      (node (ref "IC1") (pin "R12") (pinfunction "IO_L52P_M1DQ14_1_R12") (pintype "bidirectional"))
      (node (ref "IC3") (pin "63") (pinfunction "DQ14_63") (pintype "bidirectional"))
    )
    (net (code "44") (name "/DDR1_DQ15") (class "Default")
      (node (ref "IC1") (pin "T12") (pinfunction "IO_L52N_M1DQ15_1_T12") (pintype "bidirectional"))
      (node (ref "IC3") (pin "65") (pinfunction "DQ15_65") (pintype "bidirectional"))
    )
    (net (code "45") (name "/DDR1_DQSL") (class "Default")
      (node (ref "IC1") (pin "N14") (pinfunction "IO_L45P_A1_M1LDQS_1_N14") (pintype "bidirectional"))
      (node (ref "IC3") (pin "16") (pinfunction "DQSL_16") (pintype "input"))
    )
    (net (code "46") (name "/DDR1_DQSU") (class "Default")
      (node (ref "IC1") (pin "R14") (pinfunction "IO_L50P_M1UDQS_1_R14") (pintype "bidirectional"))
      (node (ref "IC3") (pin "51") (pinfunction "DQSU_51") (pintype "input"))
    )
    (net (code "47") (name "/DDR1_RAS#") (class "Default")
      (node (ref "IC1") (pin "J13") (pinfunction "IO_L41P_GCLK9_IRDY1_M1RASN_1_J13") (pintype "bidirectional"))
      (node (ref "IC3") (pin "23") (pinfunction "RAS#_23") (pintype "input"))
    )
    (net (code "48") (name "/DDR1_WE#") (class "Default")
      (node (ref "IC1") (pin "E15") (pinfunction "IO_L34P_A13_M1WE_1_E15") (pintype "bidirectional"))
      (node (ref "IC3") (pin "21") (pinfunction "WE#_21") (pintype "input"))
    )
    (net (code "49") (name "/DDR3_A0") (class "Default")
      (node (ref "DDR3_0") (pin "N3") (pinfunction "A0_N3") (pintype "input"))
      (node (ref "IC1") (pin "K5") (pinfunction "IO_L47P_M3A0_3_K5") (pintype "bidirectional"))
    )
    (net (code "50") (name "/DDR3_A1") (class "Default")
      (node (ref "DDR3_0") (pin "P7") (pinfunction "A1_P7") (pintype "input"))
      (node (ref "IC1") (pin "K6") (pinfunction "IO_L47N_M3A1_3_K6") (pintype "bidirectional"))
    )
    (net (code "51") (name "/DDR3_A2") (class "Default")
      (node (ref "DDR3_0") (pin "P3") (pinfunction "A2_P3") (pintype "input"))
      (node (ref "IC1") (pin "D1") (pinfunction "IO_L49N_M3A2_3_D1") (pintype "bidirectional"))
    )
    (net (code "52") (name "/DDR3_A3") (class "Default")
      (node (ref "DDR3_0") (pin "N2") (pinfunction "A3_N2") (pintype "input"))
      (node (ref "IC1") (pin "L4") (pinfunction "IO_L45P_M3A3_3_L4") (pintype "bidirectional"))
    )
    (net (code "53") (name "/DDR3_A4") (class "Default")
      (node (ref "DDR3_0") (pin "P8") (pinfunction "A4_P8") (pintype "input"))
      (node (ref "IC1") (pin "G5") (pinfunction "IO_L51N_M3A4_3_G5") (pintype "bidirectional"))
    )
    (net (code "54") (name "/DDR3_A5") (class "Default")
      (node (ref "DDR3_0") (pin "P2") (pinfunction "A5_P2") (pintype "input"))
      (node (ref "IC1") (pin "H4") (pinfunction "IO_L44P_GCLK21_M3A5_3_H4") (pintype "bidirectional"))
    )
    (net (code "55") (name "/DDR3_A6") (class "Default")
      (node (ref "DDR3_0") (pin "R8") (pinfunction "A6_R8") (pintype "input"))
      (node (ref "IC1") (pin "H3") (pinfunction "IO_L44N_GCLK20_M3A6_3_H3") (pintype "bidirectional"))
    )
    (net (code "56") (name "/DDR3_A7") (class "Default")
      (node (ref "DDR3_0") (pin "R2") (pinfunction "A7_R2") (pintype "input"))
      (node (ref "IC1") (pin "D3") (pinfunction "IO_L49P_M3A7_3_D3") (pintype "bidirectional"))
    )
    (net (code "57") (name "/DDR3_A8") (class "Default")
      (node (ref "DDR3_0") (pin "T8") (pinfunction "A8_T8") (pintype "input"))
      (node (ref "IC1") (pin "B2") (pinfunction "IO_L52P_M3A8_3_B2") (pintype "bidirectional"))
    )
    (net (code "58") (name "/DDR3_A9") (class "Default")
      (node (ref "DDR3_0") (pin "R3") (pinfunction "A9_R3") (pintype "input"))
      (node (ref "IC1") (pin "A2") (pinfunction "IO_L52N_M3A9_3_A2") (pintype "bidirectional"))
    )
    (net (code "59") (name "/DDR3_A10") (class "Default")
      (node (ref "DDR3_0") (pin "L7") (pinfunction "A10_L7") (pintype "input"))
      (node (ref "IC1") (pin "G6") (pinfunction "IO_L51P_M3A10_3_G6") (pintype "bidirectional"))
    )
    (net (code "60") (name "/DDR3_A11") (class "Default")
      (node (ref "DDR3_0") (pin "R7") (pinfunction "A11_R7") (pintype "input"))
      (node (ref "IC1") (pin "E3") (pinfunction "IO_L54N_M3A11_3_E3") (pintype "bidirectional"))
    )
    (net (code "61") (name "/DDR3_A12") (class "Default")
      (node (ref "DDR3_0") (pin "N7") (pinfunction "A12_N7") (pintype "input"))
      (node (ref "IC1") (pin "F3") (pinfunction "IO_L53N_M3A12_3_F3") (pintype "bidirectional"))
    )
    (net (code "62") (name "/DDR3_A13") (class "Default")
      (node (ref "DDR3_0") (pin "T3") (pinfunction "A13_T3") (pintype "input"))
      (node (ref "IC1") (pin "F6") (pinfunction "IO_L55P_M3A13_3_F6") (pintype "bidirectional"))
    )
    (net (code "63") (name "/DDR3_A14") (class "Default")
      (node (ref "DDR3_0") (pin "T7") (pinfunction "A14_T7") (pintype "input"))
      (node (ref "IC1") (pin "F5") (pinfunction "IO_L55N_M3A14_3_F5") (pintype "bidirectional"))
    )
    (net (code "64") (name "/DDR3_BA0") (class "Default")
      (node (ref "DDR3_0") (pin "M2") (pinfunction "BA0_M2") (pintype "input"))
      (node (ref "IC1") (pin "C3") (pinfunction "IO_L48P_M3BA0_3_C3") (pintype "bidirectional"))
    )
    (net (code "65") (name "/DDR3_BA1") (class "Default")
      (node (ref "DDR3_0") (pin "N8") (pinfunction "BA1_N8") (pintype "input"))
      (node (ref "IC1") (pin "C2") (pinfunction "IO_L48N_M3BA1_3_C2") (pintype "bidirectional"))
    )
    (net (code "66") (name "/DDR3_BA2") (class "Default")
      (node (ref "DDR3_0") (pin "M3") (pinfunction "BA2_M3") (pintype "input"))
      (node (ref "IC1") (pin "B1") (pinfunction "IO_L50N_M3BA2_3_B1") (pintype "bidirectional"))
    )
    (net (code "67") (name "/DDR3_CAS#") (class "Default")
      (node (ref "DDR3_0") (pin "K3") (pinfunction "CAS#_K3") (pintype "input"))
      (node (ref "IC1") (pin "H5") (pinfunction "IO_L43N_GCLK22_IRDY2_M3CASN_3_H5") (pintype "bidirectional"))
    )
    (net (code "68") (name "/DDR3_CK") (class "Default")
      (node (ref "DDR3_0") (pin "J7") (pinfunction "CK_J7") (pintype "input"))
      (node (ref "IC1") (pin "E2") (pinfunction "IO_L46P_M3CLK_3_E2") (pintype "bidirectional"))
      (node (ref "R21") (pin "2") (pinfunction "2_2") (pintype "passive"))
    )
    (net (code "69") (name "/DDR3_CK#") (class "Default")
      (node (ref "DDR3_0") (pin "K7") (pinfunction "CK#_K7") (pintype "input"))
      (node (ref "IC1") (pin "E1") (pinfunction "IO_L46N_M3CLKN_3_E1") (pintype "bidirectional"))
      (node (ref "R21") (pin "1") (pinfunction "1_1") (pintype "passive"))
    )
    (net (code "70") (name "/DDR3_CKE") (class "Default")
      (node (ref "DDR3_0") (pin "K9") (pinfunction "CKE_K9") (pintype "input"))
      (node (ref "IC1") (pin "F4") (pinfunction "IO_L53P_M3CKE_3_F4") (pintype "bidirectional"))
      (node (ref "R40") (pin "2") (pinfunction "2_2") (pintype "passive"))
    )
    (net (code "71") (name "/DDR3_DML") (class "Default")
      (node (ref "DDR3_0") (pin "E7") (pinfunction "DML_E7") (pintype "input"))
      (node (ref "IC1") (pin "J4") (pinfunction "IO_L42N_GCLK24_M3LDM_3_J4") (pintype "bidirectional"))
    )
    (net (code "72") (name "/DDR3_DMU") (class "Default")
      (node (ref "DDR3_0") (pin "D3") (pinfunction "DMU_D3") (pintype "input"))
      (node (ref "IC1") (pin "K3") (pinfunction "IO_L42P_GCLK25_TRDY2_M3UDM_3_K3") (pintype "bidirectional"))
    )
    (net (code "73") (name "/DDR3_DQ0") (class "Default")
      (node (ref "DDR3_0") (pin "E3") (pinfunction "DQ0_E3") (pintype "bidirectional"))
      (node (ref "IC1") (pin "K2") (pinfunction "IO_L37P_M3DQ0_3_K2") (pintype "bidirectional"))
    )
    (net (code "74") (name "/DDR3_DQ1") (class "Default")
      (node (ref "DDR3_0") (pin "F2") (pinfunction "DQ2_F2") (pintype "bidirectional"))
      (node (ref "IC1") (pin "K1") (pinfunction "IO_L37N_M3DQ1_3_K1") (pintype "bidirectional"))
    )
    (net (code "75") (name "/DDR3_DQ2") (class "Default")
      (node (ref "DDR3_0") (pin "F7") (pinfunction "DQ1_F7") (pintype "bidirectional"))
      (node (ref "IC1") (pin "J3") (pinfunction "IO_L38P_M3DQ2_3_J3") (pintype "bidirectional"))
    )
    (net (code "76") (name "/DDR3_DQ3") (class "Default")
      (node (ref "DDR3_0") (pin "F8") (pinfunction "DQ3_F8") (pintype "bidirectional"))
      (node (ref "IC1") (pin "J1") (pinfunction "IO_L38N_M3DQ3_3_J1") (pintype "bidirectional"))
    )
    (net (code "77") (name "/DDR3_DQ4") (class "Default")
      (node (ref "DDR3_0") (pin "H3") (pinfunction "DQ4_H3") (pintype "bidirectional"))
      (node (ref "IC1") (pin "F2") (pinfunction "IO_L41P_GCLK27_M3DQ4_3_F2") (pintype "bidirectional"))
    )
    (net (code "78") (name "/DDR3_DQ5") (class "Default")
      (node (ref "DDR3_0") (pin "H8") (pinfunction "DQ5_H8") (pintype "bidirectional"))
      (node (ref "IC1") (pin "F1") (pinfunction "IO_L41N_GCLK26_M3DQ5_3_F1") (pintype "bidirectional"))
    )
    (net (code "79") (name "/DDR3_DQ6") (class "Default")
      (node (ref "DDR3_0") (pin "G2") (pinfunction "DQ6_G2") (pintype "bidirectional"))
      (node (ref "IC1") (pin "G3") (pinfunction "IO_L40P_M3DQ6_3_G3") (pintype "bidirectional"))
    )
    (net (code "80") (name "/DDR3_DQ7") (class "Default")
      (node (ref "DDR3_0") (pin "H7") (pinfunction "DQ7_H7") (pintype "bidirectional"))
      (node (ref "IC1") (pin "G1") (pinfunction "IO_L40N_M3DQ7_3_G1") (pintype "bidirectional"))
    )
    (net (code "81") (name "/DDR3_DQ8") (class "Default")
      (node (ref "DDR3_0") (pin "C2") (pinfunction "DQ11_C2") (pintype "bidirectional"))
      (node (ref "IC1") (pin "L3") (pinfunction "IO_L36P_M3DQ8_3_L3") (pintype "bidirectional"))
    )
    (net (code "82") (name "/DDR3_DQ9") (class "Default")
      (node (ref "DDR3_0") (pin "C3") (pinfunction "DQ9_C3") (pintype "bidirectional"))
      (node (ref "IC1") (pin "L1") (pinfunction "IO_L36N_M3DQ9_3_L1") (pintype "bidirectional"))
    )
    (net (code "83") (name "/DDR3_DQ10") (class "Default")
      (node (ref "DDR3_0") (pin "A3") (pinfunction "DQ15_A3") (pintype "bidirectional"))
      (node (ref "IC1") (pin "M2") (pinfunction "IO_L35P_M3DQ10_3_M2") (pintype "bidirectional"))
    )
    (net (code "84") (name "/DDR3_DQ11") (class "Default")
      (node (ref "DDR3_0") (pin "A2") (pinfunction "DQ13_A2") (pintype "bidirectional"))
      (node (ref "IC1") (pin "M1") (pinfunction "IO_L35N_M3DQ11_3_M1") (pintype "bidirectional"))
    )
    (net (code "85") (name "/DDR3_DQ12") (class "Default")
      (node (ref "DDR3_0") (pin "C8") (pinfunction "DQ10_C8") (pintype "bidirectional"))
      (node (ref "IC1") (pin "P2") (pinfunction "IO_L33P_M3DQ12_3_P2") (pintype "bidirectional"))
    )
    (net (code "86") (name "/DDR3_DQ13") (class "Default")
      (node (ref "DDR3_0") (pin "D7") (pinfunction "DQ8_D7") (pintype "bidirectional"))
      (node (ref "IC1") (pin "P1") (pinfunction "IO_L33N_M3DQ13_3_P1") (pintype "bidirectional"))
    )
    (net (code "87") (name "/DDR3_DQ14") (class "Default")
      (node (ref "DDR3_0") (pin "B8") (pinfunction "DQ14_B8") (pintype "bidirectional"))
      (node (ref "IC1") (pin "R2") (pinfunction "IO_L32P_M3DQ14_3_R2") (pintype "bidirectional"))
    )
    (net (code "88") (name "/DDR3_DQ15") (class "Default")
      (node (ref "DDR3_0") (pin "A7") (pinfunction "DQ12_A7") (pintype "bidirectional"))
      (node (ref "IC1") (pin "R1") (pinfunction "IO_L32N_M3DQ15_3_R1") (pintype "bidirectional"))
    )
    (net (code "89") (name "/DDR3_DQSL") (class "Default")
      (node (ref "DDR3_0") (pin "F3") (pinfunction "DQSL_F3") (pintype "input"))
      (node (ref "IC1") (pin "H2") (pinfunction "IO_L39P_M3LDQS_3_H2") (pintype "bidirectional"))
    )
    (net (code "90") (name "/DDR3_DQSL#") (class "Default")
      (node (ref "DDR3_0") (pin "G3") (pinfunction "DQSL#_G3") (pintype "input"))
      (node (ref "IC1") (pin "H1") (pinfunction "IO_L39N_M3LDQSN_3_H1") (pintype "bidirectional"))
    )
    (net (code "91") (name "/DDR3_DQSU") (class "Default")
      (node (ref "DDR3_0") (pin "C7") (pinfunction "DQSU_C7") (pintype "input"))
      (node (ref "IC1") (pin "N3") (pinfunction "IO_L34P_M3UDQS_3_N3") (pintype "bidirectional"))
    )
    (net (code "92") (name "/DDR3_DQSU#") (class "Default")
      (node (ref "DDR3_0") (pin "B7") (pinfunction "DQSU#_B7") (pintype "input"))
      (node (ref "IC1") (pin "N1") (pinfunction "IO_L34N_M3UDQSN_3_N1") (pintype "bidirectional"))
    )
    (net (code "93") (name "/DDR3_ODT") (class "Default")
      (node (ref "DDR3_0") (pin "K1") (pinfunction "ODT_K1") (pintype "bidirectional"))
      (node (ref "IC1") (pin "L5") (pinfunction "IO_L45N_M3ODT_3_L5") (pintype "bidirectional"))
      (node (ref "R41") (pin "2") (pinfunction "2_2") (pintype "passive"))
    )
    (net (code "94") (name "/DDR3_RAS#") (class "Default")
      (node (ref "DDR3_0") (pin "J3") (pinfunction "RAS#_J3") (pintype "input"))
      (node (ref "IC1") (pin "J6") (pinfunction "IO_L43P_GCLK23_M3RASN_3_J6") (pintype "bidirectional"))
    )
    (net (code "95") (name "/DDR3_RESET#") (class "Default")
      (node (ref "DDR3_0") (pin "T2") (pinfunction "RESET#_T2") (pintype "input"))
      (node (ref "IC1") (pin "E4") (pinfunction "IO_L54P_M3RESET_3_E4") (pintype "bidirectional"))
      (node (ref "R44") (pin "2") (pinfunction "2_2") (pintype "passive"))
    )
    (net (code "96") (name "/DDR3_WE#") (class "Default")
      (node (ref "DDR3_0") (pin "L3") (pinfunction "WE#_L3") (pintype "input"))
      (node (ref "IC1") (pin "C1") (pinfunction "IO_L50P_M3WE_3_C1") (pintype "bidirectional"))
    )
    (net (code "97") (name "/DONE") (class "Default")
      (node (ref "IC1") (pin "P13") (pinfunction "DONE_2_P13") (pintype "bidirectional"))
      (node (ref "R29") (pin "1") (pinfunction "1_1") (pintype "passive"))
      (node (ref "R38") (pin "2") (pinfunction "2_2") (pintype "passive"))
    )
    (net (code "98") (name "/HSWAPEN") (class "Default")
      (node (ref "IC1") (pin "C4") (pinfunction "IO_L1P_HSWAPEN_0_C4") (pintype "bidirectional"))
      (node (ref "SB5") (pin "L1") (pinfunction "P$1_L1") (pintype "passive"))
    )
    (net (code "99") (name "/HSYNC") (class "Default")
      (node (ref "IC1") (pin "T4") (pinfunction "IO_L63N_2_T4") (pintype "bidirectional"))
      (node (ref "R2") (pin "2") (pinfunction "2_2") (pintype "passive"))
    )
    (net (code "100") (name "/L0") (class "Default")
      (node (ref "IC1") (pin "A8") (pinfunction "IO_L33N_0_A8") (pintype "bidirectional"))
      (node (ref "R25") (pin "1") (pinfunction "1_1") (pintype "passive"))
    )
    (net (code "101") (name "/L1") (class "Default")
      (node (ref "IC1") (pin "A7") (pinfunction "IO_L6N_0_A7") (pintype "bidirectional"))
      (node (ref "R19") (pin "1") (pinfunction "1_1") (pintype "passive"))
    )
    (net (code "102") (name "/L2") (class "Default")
      (node (ref "IC1") (pin "A6") (pinfunction "IO_L4N_0_A6") (pintype "bidirectional"))
      (node (ref "R24") (pin "1") (pinfunction "1_1") (pintype "passive"))
    )
    (net (code "103") (name "/MB_A0") (class "Default")
      (node (ref "IC1") (pin "A12") (pinfunction "IO_L62N_VREF_0_A12") (pintype "bidirectional"))
      (node (ref "U$3") (pin "A15") (pinfunction "A0_A15") (pintype "bidirectional"))
    )
    (net (code "104") (name "/MB_A1") (class "Default")
      (node (ref "IC1") (pin "D12") (pinfunction "IO_L66N_SCP0_0_D12") (pintype "bidirectional"))
      (node (ref "U$3") (pin "A16") (pinfunction "A1_A16") (pintype "bidirectional"))
    )
    (net (code "105") (name "/MB_A2") (class "Default")
      (node (ref "IC1") (pin "C11") (pinfunction "IO_L39P_0_C11") (pintype "bidirectional"))
      (node (ref "U$3") (pin "A17") (pinfunction "A2_A17") (pintype "bidirectional"))
    )
    (net (code "106") (name "/MB_A3") (class "Default")
      (node (ref "SB2") (pin "L1") (pinfunction "P$1_L1") (pintype "passive"))
      (node (ref "U$3") (pin "A18") (pinfunction "A3_A18") (pintype "bidirectional"))
    )
    (net (code "107") (name "/MB_B0") (class "Default")
      (node (ref "IC1") (pin "B12") (pinfunction "IO_L62P_0_B12") (pintype "bidirectional"))
      (node (ref "U$3") (pin "B15") (pinfunction "B0_B15") (pintype "bidirectional"))
    )
    (net (code "108") (name "/MB_B1") (class "Default")
      (node (ref "IC1") (pin "A11") (pinfunction "IO_L39N_0_A11") (pintype "bidirectional"))
      (node (ref "U$3") (pin "B16") (pinfunction "B1_B16") (pintype "bidirectional"))
    )
    (net (code "109") (name "/MB_B2") (class "Default")
      (node (ref "IC1") (pin "A10") (pinfunction "IO_L35N_GCLK16_0_A10") (pintype "bidirectional"))
      (node (ref "U$3") (pin "B17") (pinfunction "B2_B17") (pintype "bidirectional"))
    )
    (net (code "110") (name "/MB_B3") (class "Default")
      (node (ref "IC1") (pin "B10") (pinfunction "IO_L35P_GCLK17_0_B10") (pintype "bidirectional"))
      (node (ref "U$3") (pin "B18") (pinfunction "B3_B18") (pintype "bidirectional"))
    )
    (net (code "111") (name "/MB_C2") (class "Default")
      (node (ref "IC1") (pin "A14") (pinfunction "IO_L65N_SCP2_0_A14") (pintype "bidirectional"))
      (node (ref "U$3") (pin "A12") (pinfunction "C2_A12") (pintype "bidirectional"))
    )
    (net (code "112") (name "/MB_C3") (class "Default")
      (node (ref "IC1") (pin "C13") (pinfunction "IO_L63P_SCP7_0_C13") (pintype "bidirectional"))
      (node (ref "U$3") (pin "A13") (pinfunction "C3_A13") (pintype "bidirectional"))
    )
    (net (code "113") (name "/MB_D2") (class "Default")
      (node (ref "IC1") (pin "B14") (pinfunction "IO_L65P_SCP3_0_B14") (pintype "bidirectional"))
      (node (ref "U$3") (pin "B12") (pinfunction "D2_B12") (pintype "bidirectional"))
    )
    (net (code "114") (name "/MB_D3") (class "Default")
      (node (ref "IC1") (pin "A13") (pinfunction "IO_L63N_SCP6_0_A13") (pintype "bidirectional"))
      (node (ref "U$3") (pin "B13") (pinfunction "D3_B13") (pintype "bidirectional"))
    )
    (net (code "115") (name "/PROGRAM") (class "Default")
      (node (ref "IC1") (pin "T2") (pinfunction "PROGRAM_B_2_T2") (pintype "input"))
      (node (ref "R31") (pin "1") (pinfunction "1_1") (pintype "passive"))
      (node (ref "R48") (pin "2") (pinfunction "2_2") (pintype "passive"))
      (node (ref "S1") (pin "2") (pinfunction "2_2") (pintype "passive"))
    )
    (net (code "116") (name "/TCK_B") (class "Default")
      (node (ref "IC1") (pin "C14") (pinfunction "TCK_C14") (pintype "input"))
      (node (ref "IC2") (pin "5") (pinfunction "2Y_5") (pintype "bidirectional"))
    )
    (net (code "117") (name "/TCK_I") (class "Default")
      (node (ref "IC2") (pin "3") (pinfunction "2A_3") (pintype "bidirectional"))
      (node (ref "U$3") (pin "B2") (pinfunction "TCK_B2") (pintype "bidirectional"))
    )
    (net (code "118") (name "/TDI_B") (class "Default")
      (node (ref "IC1") (pin "C12") (pinfunction "TDI_C12") (pintype "input"))
      (node (ref "IC2") (pin "7") (pinfunction "1Y_7") (pintype "bidirectional"))
    )
    (net (code "119") (name "/TDI_I") (class "Default")
      (node (ref "IC2") (pin "1") (pinfunction "1A_1") (pintype "bidirectional"))
      (node (ref "U$3") (pin "B1") (pinfunction "TDI_B1") (pintype "output"))
    )
    (net (code "120") (name "/TDO") (class "Default")
      (node (ref "IC1") (pin "E14") (pinfunction "TDO_E14") (pintype "output"))
      (node (ref "U$3") (pin "A1") (pinfunction "TDO_A1") (pintype "input"))
    )
    (net (code "121") (name "/TMS_B") (class "Default")
      (node (ref "IC1") (pin "A15") (pinfunction "TMS_A15") (pintype "input"))
      (node (ref "IC2") (pin "2") (pinfunction "3Y_2") (pintype "bidirectional"))
    )
    (net (code "122") (name "/TMS_I") (class "Default")
      (node (ref "IC2") (pin "6") (pinfunction "3A_6") (pintype "bidirectional"))
      (node (ref "U$3") (pin "A2") (pinfunction "TMS_A2") (pintype "bidirectional"))
    )
    (net (code "123") (name "/USB_CLK") (class "Default")
      (node (ref "IC1") (pin "E10") (pinfunction "IO_L37P_GCLK13_0_E10") (pintype "bidirectional"))
      (node (ref "U$20") (pin "21") (pinfunction "REFCLK/XI_21") (pintype "bidirectional"))
    )
    (net (code "124") (name "/USB_DATA0") (class "Default")
      (node (ref "IC1") (pin "M10") (pinfunction "IO_L16N_VREF_2_M10") (pintype "bidirectional"))
      (node (ref "U$20") (pin "4") (pinfunction "DATA0_4") (pintype "bidirectional"))
    )
    (net (code "125") (name "/USB_DATA1") (class "Default")
      (node (ref "IC1") (pin "N9") (pinfunction "IO_L14P_D11_2_N9") (pintype "bidirectional"))
      (node (ref "U$20") (pin "5") (pinfunction "DATA1_5") (pintype "bidirectional"))
    )
    (net (code "126") (name "/USB_DATA2") (class "Default")
      (node (ref "IC1") (pin "L10") (pinfunction "IO_L16P_2_L10") (pintype "bidirectional"))
      (node (ref "U$20") (pin "6") (pinfunction "DATA2_6") (pintype "bidirectional"))
    )
    (net (code "127") (name "/USB_DATA3") (class "Default")
      (node (ref "IC1") (pin "P9") (pinfunction "IO_L14N_D12_2_P9") (pintype "bidirectional"))
      (node (ref "U$20") (pin "7") (pinfunction "DATA3_7") (pintype "bidirectional"))
    )
    (net (code "128") (name "/USB_DATA4") (class "Default")
      (node (ref "IC1") (pin "M9") (pinfunction "IO_L29P_GCLK3_2_M9") (pintype "bidirectional"))
      (node (ref "U$20") (pin "8") (pinfunction "DATA4_8") (pintype "bidirectional"))
    )
    (net (code "129") (name "/USB_DATA5") (class "Default")
      (node (ref "IC1") (pin "R9") (pinfunction "IO_L23P_2_R9") (pintype "bidirectional"))
      (node (ref "U$20") (pin "10") (pinfunction "DATA5_10") (pintype "bidirectional"))
    )
    (net (code "130") (name "/USB_DATA6") (class "Default")
      (node (ref "IC1") (pin "T9") (pinfunction "IO_L23N_2_T9") (pintype "bidirectional"))
      (node (ref "U$20") (pin "11") (pinfunction "DATA6_11") (pintype "bidirectional"))
    )
    (net (code "131") (name "/USB_DATA7") (class "Default")
      (node (ref "IC1") (pin "N8") (pinfunction "IO_L29N_GCLK2_2_N8") (pintype "bidirectional"))
      (node (ref "U$20") (pin "12") (pinfunction "DATA7_12") (pintype "bidirectional"))
    )
    (net (code "132") (name "/USB_DIR") (class "Default")
      (node (ref "IC1") (pin "L8") (pinfunction "IO_L62P_D5_2_L8") (pintype "bidirectional"))
      (node (ref "U$20") (pin "1") (pinfunction "DIR_1") (pintype "bidirectional"))
    )
    (net (code "133") (name "/USB_NXT") (class "Default")
      (node (ref "IC1") (pin "P11") (pinfunction "IO_L13N_D10_2_P11") (pintype "bidirectional"))
      (node (ref "U$20") (pin "3") (pinfunction "NXT_3") (pintype "bidirectional"))
    )
    (net (code "134") (name "/USB_RESET") (class "Default")
      (node (ref "IC1") (pin "M12") (pinfunction "IO_L2P_CMPCLK_2_M12") (pintype "bidirectional"))
      (node (ref "U$20") (pin "22") (pinfunction "RESETB_22") (pintype "bidirectional"))
    )
    (net (code "135") (name "/USB_STP") (class "Default")
      (node (ref "IC1") (pin "M11") (pinfunction "IO_L2N_CMPMOSI_2_M11") (pintype "bidirectional"))
      (node (ref "U$20") (pin "24") (pinfunction "STP_24") (pintype "bidirectional"))
    )
    (net (code "136") (name "/VB0") (class "Default")
      (node (ref "IC1") (pin "P5") (pinfunction "IO_L49N_D4_2_P5") (pintype "bidirectional"))
      (node (ref "R9") (pin "1") (pinfunction "1_1") (pintype "passive"))
    )
    (net (code "137") (name "/VB1") (class "Default")
      (node (ref "IC1") (pin "P6") (pinfunction "IO_L47P_2_P6") (pintype "bidirectional"))
      (node (ref "R3") (pin "1") (pinfunction "1_1") (pintype "passive"))
    )
    (net (code "138") (name "/VB2") (class "Default")
      (node (ref "IC1") (pin "N6") (pinfunction "IO_L64N_D9_2_N6") (pintype "bidirectional"))
      (node (ref "R12") (pin "1") (pinfunction "1_1") (pintype "passive"))
    )
    (net (code "139") (name "/VB3") (class "Default")
      (node (ref "IC1") (pin "M6") (pinfunction "IO_L64P_D8_2_M6") (pintype "bidirectional"))
      (node (ref "R6") (pin "1") (pinfunction "1_1") (pintype "passive"))
    )
    (net (code "140") (name "/VB4") (class "Default")
      (node (ref "IC1") (pin "N5") (pinfunction "IO_L49P_D3_2_N5") (pintype "bidirectional"))
      (node (ref "R15") (pin "1") (pinfunction "1_1") (pintype "passive"))
    )
    (net (code "141") (name "/VG0") (class "Default")
      (node (ref "IC1") (pin "P8") (pinfunction "IO_L30P_GCLK1_D13_2_P8") (pintype "bidirectional"))
      (node (ref "R10") (pin "1") (pinfunction "1_1") (pintype "passive"))
    )
    (net (code "142") (name "/VG1") (class "Default")
      (node (ref "IC1") (pin "R7") (pinfunction "IO_L32P_GCLK29_2_R7") (pintype "bidirectional"))
      (node (ref "R4") (pin "1") (pinfunction "1_1") (pintype "passive"))
    )
    (net (code "143") (name "/VG2") (class "Default")
      (node (ref "IC1") (pin "T6") (pinfunction "IO_L47N_2_T6") (pintype "bidirectional"))
      (node (ref "R13") (pin "1") (pinfunction "1_1") (pintype "passive"))
    )
    (net (code "144") (name "/VG3") (class "Default")
      (node (ref "IC1") (pin "R5") (pinfunction "IO_L48P_D7_2_R5") (pintype "bidirectional"))
      (node (ref "R7") (pin "1") (pinfunction "1_1") (pintype "passive"))
    )
    (net (code "145") (name "/VG4") (class "Default")
      (node (ref "IC1") (pin "T5") (pinfunction "IO_L48N_RDWR_B_VREF_2_T5") (pintype "bidirectional"))
      (node (ref "R16") (pin "1") (pinfunction "1_1") (pintype "passive"))
    )
    (net (code "146") (name "/VR0") (class "Default")
      (node (ref "IC1") (pin "T8") (pinfunction "IO_L30N_GCLK0_USERCCLK_2_T8") (pintype "bidirectional"))
      (node (ref "R17") (pin "1") (pinfunction "1_1") (pintype "passive"))
    )
    (net (code "147") (name "/VR1") (class "Default")
      (node (ref "IC1") (pin "T7") (pinfunction "IO_L32N_GCLK28_2_T7") (pintype "bidirectional"))
      (node (ref "R11") (pin "1") (pinfunction "1_1") (pintype "passive"))
    )
    (net (code "148") (name "/VR2") (class "Default")
      (node (ref "IC1") (pin "L7") (pinfunction "IO_L62N_D6_2_L7") (pintype "bidirectional"))
      (node (ref "R5") (pin "1") (pinfunction "1_1") (pintype "passive"))
    )
    (net (code "149") (name "/VR3") (class "Default")
      (node (ref "IC1") (pin "P7") (pinfunction "IO_L31P_GCLK31_D14_2_P7") (pintype "bidirectional"))
      (node (ref "R14") (pin "1") (pinfunction "1_1") (pintype "passive"))
    )
    (net (code "150") (name "/VR4") (class "Default")
      (node (ref "IC1") (pin "M7") (pinfunction "IO_L31N_GCLK30_D15_2_M7") (pintype "bidirectional"))
      (node (ref "R8") (pin "1") (pinfunction "1_1") (pintype "passive"))
    )
    (net (code "151") (name "/VREF_DDR1") (class "Default")
      (node (ref "C27") (pin "1") (pinfunction "1_1") (pintype "passive"))
      (node (ref "C30") (pin "2") (pinfunction "2_2") (pintype "passive"))
      (node (ref "IC1") (pin "E12") (pinfunction "IO_L1N_A24_VREF_1_E12") (pintype "bidirectional"))
      (node (ref "IC1") (pin "L13") (pinfunction "IO_L53N_VREF_1_L13") (pintype "bidirectional"))
      (node (ref "IC3") (pin "49") (pinfunction "VREF_49") (pintype "input"))
      (node (ref "R37") (pin "2") (pinfunction "2_2") (pintype "passive"))
      (node (ref "R39") (pin "1") (pinfunction "1_1") (pintype "passive"))
    )
    (net (code "152") (name "/VREF_DDR3") (class "Default")
      (node (ref "C7") (pin "1") (pinfunction "1_1") (pintype "passive"))
      (node (ref "C8") (pin "2") (pinfunction "2_2") (pintype "passive"))
      (node (ref "DDR3_0") (pin "H1") (pinfunction "VREFDQ_H1") (pintype "input"))
      (node (ref "DDR3_0") (pin "M8") (pinfunction "VREFCA_M8") (pintype "input"))
      (node (ref "IC1") (pin "A3") (pinfunction "IO_L83N_VREF_3_A3") (pintype "bidirectional"))
      (node (ref "IC1") (pin "M3") (pinfunction "IO_L1N_VREF_3_M3") (pintype "bidirectional"))
      (node (ref "R18") (pin "2") (pinfunction "2_2") (pintype "passive"))
      (node (ref "R36") (pin "1") (pinfunction "1_1") (pintype "passive"))
    )
    (net (code "153") (name "/VSYNC") (class "Default")
      (node (ref "IC1") (pin "P4") (pinfunction "IO_L63P_2_P4") (pintype "bidirectional"))
      (node (ref "R1") (pin "2") (pinfunction "2_2") (pintype "passive"))
    )
    (net (code "154") (name "/~{GRST}") (class "Default")
      (node (ref "SB1") (pin "L1") (pinfunction "P$1_L1") (pintype "passive"))
      (node (ref "SB1") (pin "L2") (pinfunction "P$1_L2") (pintype "passive"))
      (node (ref "U$3") (pin "B5") (pinfunction "~{GRST}_B5") (pintype "bidirectional"))
    )
    (net (code "155") (name "1.2V") (class "Default")
      (node (ref "C20") (pin "1") (pinfunction "+_1") (pintype "passive"))
      (node (ref "C24") (pin "1") (pinfunction "1_1") (pintype "passive"))
      (node (ref "C25") (pin "1") (pinfunction "1_1") (pintype "passive"))
      (node (ref "C26") (pin "1") (pinfunction "1_1") (pintype "passive"))
      (node (ref "C43") (pin "1") (pinfunction "1_1") (pintype "passive"))
      (node (ref "CONN3") (pin "P") (pinfunction "P_P") (pintype "bidirectional"))
      (node (ref "IC1") (pin "G7") (pinfunction "VCCINT_G7") (pintype "input"))
      (node (ref "IC1") (pin "G9") (pinfunction "VCCINT_G9") (pintype "input"))
      (node (ref "IC1") (pin "H10") (pinfunction "VCCINT_H10") (pintype "input"))
      (node (ref "IC1") (pin "H8") (pinfunction "VCCINT_H8") (pintype "input"))
      (node (ref "IC1") (pin "J7") (pinfunction "VCCINT_J7") (pintype "input"))
      (node (ref "IC1") (pin "J9") (pinfunction "VCCINT_J9") (pintype "input"))
      (node (ref "IC1") (pin "K10") (pinfunction "VCCINT_K10") (pintype "input"))
      (node (ref "IC1") (pin "K8") (pinfunction "VCCINT_K8") (pintype "input"))
      (node (ref "U$11") (pin "2") (pinfunction "OUT_2") (pintype "passive"))
      (node (ref "U$11") (pin "4") (pinfunction "OUT_4") (pintype "passive"))
    )
    (net (code "156") (name "1.5V") (class "Default")
      (node (ref "C1") (pin "1") (pinfunction "1_1") (pintype "passive"))
      (node (ref "C2") (pin "1") (pinfunction "1_1") (pintype "passive"))
      (node (ref "C33") (pin "1") (pinfunction "1_1") (pintype "passive"))
      (node (ref "C34") (pin "1") (pinfunction "1_1") (pintype "passive"))
      (node (ref "C35") (pin "1") (pinfunction "1_1") (pintype "passive"))
      (node (ref "C36") (pin "1") (pinfunction "1_1") (pintype "passive"))
      (node (ref "C37") (pin "1") (pinfunction "1_1") (pintype "passive"))
      (node (ref "C4") (pin "1") (pinfunction "+_1") (pintype "passive"))
      (node (ref "C44") (pin "1") (pinfunction "1_1") (pintype "passive"))
      (node (ref "C46") (pin "1") (pinfunction "1_1") (pintype "passive"))
      (node (ref "C5") (pin "1") (pinfunction "1_1") (pintype "passive"))
      (node (ref "C8") (pin "1") (pinfunction "1_1") (pintype "passive"))
      (node (ref "CONN5") (pin "P") (pinfunction "P_P") (pintype "bidirectional"))
      (node (ref "DDR3_0") (pin "A1") (pinfunction "VDDQ_A1") (pintype "input"))
      (node (ref "DDR3_0") (pin "A8") (pinfunction "VDDQ_A8") (pintype "input"))
      (node (ref "DDR3_0") (pin "B2") (pinfunction "VDD_B2") (pintype "input"))
      (node (ref "DDR3_0") (pin "C1") (pinfunction "VDDQ_C1") (pintype "input"))
      (node (ref "DDR3_0") (pin "C9") (pinfunction "VDDQ_C9") (pintype "input"))
      (node (ref "DDR3_0") (pin "D2") (pinfunction "VDDQ_D2") (pintype "input"))
      (node (ref "DDR3_0") (pin "D9") (pinfunction "VDD_D9") (pintype "input"))
      (node (ref "DDR3_0") (pin "E9") (pinfunction "VDDQ_E9") (pintype "input"))
      (node (ref "DDR3_0") (pin "F1") (pinfunction "VDDQ_F1") (pintype "input"))
      (node (ref "DDR3_0") (pin "G7") (pinfunction "VDD_G7") (pintype "input"))
      (node (ref "DDR3_0") (pin "H2") (pinfunction "VDDQ_H2") (pintype "input"))
      (node (ref "DDR3_0") (pin "H9") (pinfunction "VDDQ_H9") (pintype "input"))
      (node (ref "DDR3_0") (pin "K2") (pinfunction "VDD_K2") (pintype "input"))
      (node (ref "DDR3_0") (pin "K8") (pinfunction "VDD_K8") (pintype "input"))
      (node (ref "DDR3_0") (pin "N1") (pinfunction "VDD_N1") (pintype "input"))
      (node (ref "DDR3_0") (pin "N9") (pinfunction "VDD_N9") (pintype "input"))
      (node (ref "DDR3_0") (pin "R1") (pinfunction "VDD_R1") (pintype "input"))
      (node (ref "DDR3_0") (pin "R9") (pinfunction "VDD_R9") (pintype "input"))
      (node (ref "IC1") (pin "D2") (pinfunction "VCCO_3_D2") (pintype "input"))
      (node (ref "IC1") (pin "G4") (pinfunction "VCCO_3_G4") (pintype "input"))
      (node (ref "IC1") (pin "J2") (pinfunction "VCCO_3_J2") (pintype "input"))
      (node (ref "IC1") (pin "K4") (pinfunction "VCCO_3_K4") (pintype "input"))
      (node (ref "IC1") (pin "N2") (pinfunction "VCCO_3_N2") (pintype "input"))
      (node (ref "R36") (pin "2") (pinfunction "2_2") (pintype "passive"))
      (node (ref "U$13") (pin "2") (pinfunction "OUT_2") (pintype "passive"))
      (node (ref "U$13") (pin "4") (pinfunction "OUT_4") (pintype "passive"))
    )
    (net (code "157") (name "2.5V") (class "Default")
      (node (ref "C12") (pin "1") (pinfunction "1_1") (pintype "passive"))
      (node (ref "C13") (pin "1") (pinfunction "1_1") (pintype "passive"))
      (node (ref "C14") (pin "1") (pinfunction "1_1") (pintype "passive"))
      (node (ref "C23") (pin "1") (pinfunction "1_1") (pintype "passive"))
      (node (ref "C30") (pin "1") (pinfunction "1_1") (pintype "passive"))
      (node (ref "C38") (pin "1") (pinfunction "1_1") (pintype "passive"))
      (node (ref "C39") (pin "1") (pinfunction "1_1") (pintype "passive"))
      (node (ref "C40") (pin "1") (pinfunction "1_1") (pintype "passive"))
      (node (ref "C41") (pin "1") (pinfunction "1_1") (pintype "passive"))
      (node (ref "C42") (pin "1") (pinfunction "1_1") (pintype "passive"))
      (node (ref "C45") (pin "1") (pinfunction "1_1") (pintype "passive"))
      (node (ref "C51") (pin "1") (pinfunction "1_1") (pintype "passive"))
      (node (ref "CONN2") (pin "P") (pinfunction "P_P") (pintype "bidirectional"))
      (node (ref "IC1") (pin "D15") (pinfunction "VCCO_1_D15") (pintype "input"))
      (node (ref "IC1") (pin "G13") (pinfunction "VCCO_1_G13") (pintype "input"))
      (node (ref "IC1") (pin "J15") (pinfunction "VCCO_1_J15") (pintype "input"))
      (node (ref "IC1") (pin "K13") (pinfunction "VCCO_1_K13") (pintype "input"))
      (node (ref "IC1") (pin "N15") (pinfunction "VCCO_1_N15") (pintype "input"))
      (node (ref "IC1") (pin "R13") (pinfunction "VCCO_1_R13") (pintype "input"))
      (node (ref "IC3") (pin "1") (pinfunction "VDD_1") (pintype "input"))
      (node (ref "IC3") (pin "15") (pinfunction "VDDQ_15") (pintype "input"))
      (node (ref "IC3") (pin "18") (pinfunction "VDD_18") (pintype "input"))
      (node (ref "IC3") (pin "3") (pinfunction "VDDQ_3") (pintype "input"))
      (node (ref "IC3") (pin "33") (pinfunction "VDD_33") (pintype "input"))
      (node (ref "IC3") (pin "55") (pinfunction "VDDQ_55") (pintype "input"))
      (node (ref "IC3") (pin "61") (pinfunction "VDDQ_61") (pintype "input"))
      (node (ref "IC3") (pin "9") (pinfunction "VDDQ_9") (pintype "input"))
      (node (ref "R39") (pin "2") (pinfunction "2_2") (pintype "passive"))
      (node (ref "U$14") (pin "2") (pinfunction "OUT_2") (pintype "passive"))
    )
    (net (code "158") (name "3.3V") (class "Default")
      (node (ref "C10") (pin "1") (pinfunction "1_1") (pintype "passive"))
      (node (ref "C11") (pin "1") (pinfunction "1_1") (pintype "passive"))
      (node (ref "C15") (pin "1") (pinfunction "1_1") (pintype "passive"))
      (node (ref "C16") (pin "1") (pinfunction "1_1") (pintype "passive"))
      (node (ref "C17") (pin "1") (pinfunction "1_1") (pintype "passive"))
      (node (ref "C18") (pin "1") (pinfunction "1_1") (pintype "passive"))
      (node (ref "C19") (pin "1") (pinfunction "1_1") (pintype "passive"))
      (node (ref "C21") (pin "1") (pinfunction "+_1") (pintype "passive"))
      (node (ref "C22") (pin "1") (pinfunction "1_1") (pintype "passive"))
      (node (ref "C3") (pin "1") (pinfunction "1_1") (pintype "passive"))
      (node (ref "C47") (pin "1") (pinfunction "1_1") (pintype "passive"))
      (node (ref "C54") (pin "1") (pinfunction "1_1") (pintype "passive"))
      (node (ref "C6") (pin "1") (pinfunction "1_1") (pintype "passive"))
      (node (ref "C9") (pin "1") (pinfunction "1_1") (pintype "passive"))
      (node (ref "CONN1") (pin "P") (pinfunction "P_P") (pintype "bidirectional"))
      (node (ref "IC1") (pin "B13") (pinfunction "VCCO_0_B13") (pintype "input"))
      (node (ref "IC1") (pin "B4") (pinfunction "VCCO_0_B4") (pintype "input"))
      (node (ref "IC1") (pin "B9") (pinfunction "VCCO_0_B9") (pintype "input"))
      (node (ref "IC1") (pin "D10") (pinfunction "VCCO_0_D10") (pintype "input"))
      (node (ref "IC1") (pin "D7") (pinfunction "VCCO_0_D7") (pintype "input"))
      (node (ref "IC1") (pin "E5") (pinfunction "VCCAUX_E5") (pintype "input"))
      (node (ref "IC1") (pin "F11") (pinfunction "VCCAUX_F11") (pintype "input"))
      (node (ref "IC1") (pin "F8") (pinfunction "VCCAUX_F8") (pintype "input"))
      (node (ref "IC1") (pin "G10") (pinfunction "VCCAUX_G10") (pintype "input"))
      (node (ref "IC1") (pin "H6") (pinfunction "VCCAUX_H6") (pintype "input"))
      (node (ref "IC1") (pin "J10") (pinfunction "VCCAUX_J10") (pintype "input"))
      (node (ref "IC1") (pin "L6") (pinfunction "VCCAUX_L6") (pintype "input"))
      (node (ref "IC1") (pin "L9") (pinfunction "VCCAUX_L9") (pintype "input"))
      (node (ref "IC1") (pin "N10") (pinfunction "VCCO_2_N10") (pintype "input"))
      (node (ref "IC1") (pin "N7") (pinfunction "VCCO_2_N7") (pintype "input"))
      (node (ref "IC1") (pin "R4") (pinfunction "VCCO_2_R4") (pintype "input"))
      (node (ref "IC1") (pin "R8") (pinfunction "VCCO_2_R8") (pintype "input"))
      (node (ref "IC1") (pin "T11") (pinfunction "IO_L1N_M0_CMPMISO_2_T11") (pintype "bidirectional"))
      (node (ref "IC2") (pin "8") (pinfunction "VCC_8") (pintype "bidirectional"))
      (node (ref "L0") (pin "A") (pinfunction "A_A") (pintype "passive"))
      (node (ref "L1") (pin "A") (pinfunction "A_A") (pintype "passive"))
      (node (ref "L2") (pin "A") (pinfunction "A_A") (pintype "passive"))
      (node (ref "R26") (pin "1") (pinfunction "1_1") (pintype "passive"))
      (node (ref "R27") (pin "2") (pinfunction "2_2") (pintype "passive"))
      (node (ref "R28") (pin "2") (pinfunction "2_2") (pintype "passive"))
      (node (ref "R29") (pin "2") (pinfunction "2_2") (pintype "passive"))
      (node (ref "R30") (pin "2") (pinfunction "2_2") (pintype "passive"))
      (node (ref "R31") (pin "2") (pinfunction "2_2") (pintype "passive"))
      (node (ref "R32") (pin "2") (pinfunction "2_2") (pintype "passive"))
      (node (ref "R46") (pin "2") (pinfunction "2_2") (pintype "passive"))
      (node (ref "U$10") (pin "8") (pinfunction "VCC_8") (pintype "bidirectional"))
      (node (ref "U$11") (pin "3") (pinfunction "IN_3") (pintype "input"))
      (node (ref "U$13") (pin "3") (pinfunction "IN_3") (pintype "input"))
      (node (ref "U$14") (pin "3") (pinfunction "IN_3") (pintype "input"))
      (node (ref "U$20") (pin "16") (pinfunction "VBAT_16") (pintype "input"))
      (node (ref "U$20") (pin "2") (pinfunction "CLKOUT_2") (pintype "bidirectional"))
      (node (ref "U$20") (pin "9") (pinfunction "VDDIO_9") (pintype "input"))
      (node (ref "U$6") (pin "1") (pinfunction "EN_1") (pintype "bidirectional"))
      (node (ref "U$6") (pin "4") (pinfunction "VCC_4") (pintype "bidirectional"))
    )
    (net (code "159") (name "GND") (class "Default")
      (node (ref "C1") (pin "2") (pinfunction "2_2") (pintype "passive"))
      (node (ref "C10") (pin "2") (pinfunction "2_2") (pintype "passive"))
      (node (ref "C11") (pin "2") (pinfunction "2_2") (pintype "passive"))
      (node (ref "C12") (pin "2") (pinfunction "2_2") (pintype "passive"))
      (node (ref "C13") (pin "2") (pinfunction "2_2") (pintype "passive"))
      (node (ref "C14") (pin "2") (pinfunction "2_2") (pintype "passive"))
      (node (ref "C15") (pin "2") (pinfunction "2_2") (pintype "passive"))
      (node (ref "C16") (pin "2") (pinfunction "2_2") (pintype "passive"))
      (node (ref "C17") (pin "2") (pinfunction "2_2") (pintype "passive"))
      (node (ref "C18") (pin "2") (pinfunction "2_2") (pintype "passive"))
      (node (ref "C19") (pin "2") (pinfunction "2_2") (pintype "passive"))
      (node (ref "C2") (pin "2") (pinfunction "2_2") (pintype "passive"))
      (node (ref "C20") (pin "2") (pinfunction "-_2") (pintype "passive"))
      (node (ref "C21") (pin "2") (pinfunction "-_2") (pintype "passive"))
      (node (ref "C22") (pin "2") (pinfunction "2_2") (pintype "passive"))
      (node (ref "C23") (pin "2") (pinfunction "2_2") (pintype "passive"))
      (node (ref "C24") (pin "2") (pinfunction "2_2") (pintype "passive"))
      (node (ref "C25") (pin "2") (pinfunction "2_2") (pintype "passive"))
      (node (ref "C26") (pin "2") (pinfunction "2_2") (pintype "passive"))
      (node (ref "C27") (pin "2") (pinfunction "2_2") (pintype "passive"))
      (node (ref "C3") (pin "2") (pinfunction "2_2") (pintype "passive"))
      (node (ref "C33") (pin "2") (pinfunction "2_2") (pintype "passive"))
      (node (ref "C34") (pin "2") (pinfunction "2_2") (pintype "passive"))
      (node (ref "C35") (pin "2") (pinfunction "2_2") (pintype "passive"))
      (node (ref "C36") (pin "2") (pinfunction "2_2") (pintype "passive"))
      (node (ref "C37") (pin "2") (pinfunction "2_2") (pintype "passive"))
      (node (ref "C38") (pin "2") (pinfunction "2_2") (pintype "passive"))
      (node (ref "C39") (pin "2") (pinfunction "2_2") (pintype "passive"))
      (node (ref "C4") (pin "2") (pinfunction "-_2") (pintype "passive"))
      (node (ref "C40") (pin "2") (pinfunction "2_2") (pintype "passive"))
      (node (ref "C41") (pin "2") (pinfunction "2_2") (pintype "passive"))
      (node (ref "C42") (pin "2") (pinfunction "2_2") (pintype "passive"))
      (node (ref "C43") (pin "2") (pinfunction "2_2") (pintype "passive"))
      (node (ref "C44") (pin "2") (pinfunction "2_2") (pintype "passive"))
      (node (ref "C45") (pin "2") (pinfunction "2_2") (pintype "passive"))
      (node (ref "C46") (pin "2") (pinfunction "2_2") (pintype "passive"))
      (node (ref "C47") (pin "2") (pinfunction "2_2") (pintype "passive"))
      (node (ref "C5") (pin "2") (pinfunction "2_2") (pintype "passive"))
      (node (ref "C51") (pin "2") (pinfunction "2_2") (pintype "passive"))
      (node (ref "C53") (pin "2") (pinfunction "2_2") (pintype "passive"))
      (node (ref "C54") (pin "2") (pinfunction "2_2") (pintype "passive"))
      (node (ref "C55") (pin "2") (pinfunction "2_2") (pintype "passive"))
      (node (ref "C56") (pin "2") (pinfunction "2_2") (pintype "passive"))
      (node (ref "C57") (pin "1") (pinfunction "1_1") (pintype "passive"))
      (node (ref "C6") (pin "2") (pinfunction "2_2") (pintype "passive"))
      (node (ref "C7") (pin "2") (pinfunction "2_2") (pintype "passive"))
      (node (ref "C9") (pin "2") (pinfunction "2_2") (pintype "passive"))
      (node (ref "CLIP") (pin "P$1") (pinfunction "P_P$1") (pintype "bidirectional"))
      (node (ref "CLIP") (pin "P$2") (pinfunction "P_P$2") (pintype "bidirectional"))
      (node (ref "CONN4") (pin "P") (pinfunction "P_P") (pintype "bidirectional"))
      (node (ref "DDR3_0") (pin "A9") (pinfunction "VSS_A9") (pintype "input"))
      (node (ref "DDR3_0") (pin "B1") (pinfunction "VSSQ_B1") (pintype "input"))
      (node (ref "DDR3_0") (pin "B3") (pinfunction "VSS_B3") (pintype "input"))
      (node (ref "DDR3_0") (pin "B9") (pinfunction "VSSQ_B9") (pintype "input"))
      (node (ref "DDR3_0") (pin "D1") (pinfunction "VSSQ_D1") (pintype "input"))
      (node (ref "DDR3_0") (pin "D8") (pinfunction "VSSQ_D8") (pintype "input"))
      (node (ref "DDR3_0") (pin "E1") (pinfunction "VSS_E1") (pintype "input"))
      (node (ref "DDR3_0") (pin "E2") (pinfunction "VSSQ_E2") (pintype "input"))
      (node (ref "DDR3_0") (pin "E8") (pinfunction "VSSQ_E8") (pintype "input"))
      (node (ref "DDR3_0") (pin "F9") (pinfunction "VSSQ_F9") (pintype "input"))
      (node (ref "DDR3_0") (pin "G1") (pinfunction "VSSQ_G1") (pintype "input"))
      (node (ref "DDR3_0") (pin "G8") (pinfunction "VSS_G8") (pintype "input"))
      (node (ref "DDR3_0") (pin "G9") (pinfunction "VSSQ_G9") (pintype "input"))
      (node (ref "DDR3_0") (pin "J2") (pinfunction "VSS_J2") (pintype "input"))
      (node (ref "DDR3_0") (pin "J8") (pinfunction "VSS_J8") (pintype "input"))
      (node (ref "DDR3_0") (pin "M1") (pinfunction "VSS_M1") (pintype "input"))
      (node (ref "DDR3_0") (pin "M9") (pinfunction "VSS_M9") (pintype "input"))
      (node (ref "DDR3_0") (pin "P1") (pinfunction "VSS_P1") (pintype "input"))
      (node (ref "DDR3_0") (pin "P9") (pinfunction "VSS_P9") (pintype "input"))
      (node (ref "DDR3_0") (pin "T1") (pinfunction "VSS_T1") (pintype "input"))
      (node (ref "DDR3_0") (pin "T9") (pinfunction "VSS_T9") (pintype "input"))
      (node (ref "IC1") (pin "A1") (pinfunction "GND_A1") (pintype "input"))
      (node (ref "IC1") (pin "A16") (pinfunction "GND_A16") (pintype "input"))
      (node (ref "IC1") (pin "B11") (pinfunction "GND_B11") (pintype "input"))
      (node (ref "IC1") (pin "B7") (pinfunction "GND_B7") (pintype "input"))
      (node (ref "IC1") (pin "D13") (pinfunction "GND_D13") (pintype "input"))
      (node (ref "IC1") (pin "D4") (pinfunction "GND_D4") (pintype "input"))
      (node (ref "IC1") (pin "E9") (pinfunction "GND_E9") (pintype "input"))
      (node (ref "IC1") (pin "G15") (pinfunction "GND_G15") (pintype "input"))
      (node (ref "IC1") (pin "G2") (pinfunction "GND_G2") (pintype "input"))
      (node (ref "IC1") (pin "G8") (pinfunction "GND_G8") (pintype "input"))
      (node (ref "IC1") (pin "H12") (pinfunction "GND_H12") (pintype "input"))
      (node (ref "IC1") (pin "H7") (pinfunction "GND_H7") (pintype "input"))
      (node (ref "IC1") (pin "H9") (pinfunction "GND_H9") (pintype "input"))
      (node (ref "IC1") (pin "J5") (pinfunction "GND_J5") (pintype "input"))
      (node (ref "IC1") (pin "J8") (pinfunction "GND_J8") (pintype "input"))
      (node (ref "IC1") (pin "K7") (pinfunction "GND_K7") (pintype "input"))
      (node (ref "IC1") (pin "K9") (pinfunction "GND_K9") (pintype "input"))
      (node (ref "IC1") (pin "L15") (pinfunction "GND_L15") (pintype "input"))
      (node (ref "IC1") (pin "L2") (pinfunction "GND_L2") (pintype "input"))
      (node (ref "IC1") (pin "M8") (pinfunction "GND_M8") (pintype "input"))
      (node (ref "IC1") (pin "N11") (pinfunction "IO_L13P_M1_2_N11") (pintype "bidirectional"))
      (node (ref "IC1") (pin "N13") (pinfunction "GND_N13") (pintype "input"))
      (node (ref "IC1") (pin "P14") (pinfunction "SUSPEND_P14") (pintype "input"))
      (node (ref "IC1") (pin "P3") (pinfunction "GND_P3") (pintype "input"))
      (node (ref "IC1") (pin "R10") (pinfunction "GND_R10") (pintype "input"))
      (node (ref "IC1") (pin "R6") (pinfunction "GND_R6") (pintype "input"))
      (node (ref "IC1") (pin "T1") (pinfunction "GND_T1") (pintype "input"))
      (node (ref "IC1") (pin "T16") (pinfunction "GND_T16") (pintype "input"))
      (node (ref "IC2") (pin "4") (pinfunction "GND_4") (pintype "bidirectional"))
      (node (ref "IC3") (pin "12") (pinfunction "VSSQ_12") (pintype "input"))
      (node (ref "IC3") (pin "34") (pinfunction "VSS_34") (pintype "input"))
      (node (ref "IC3") (pin "48") (pinfunction "VSS_48") (pintype "input"))
      (node (ref "IC3") (pin "52") (pinfunction "VSSQ_52") (pintype "input"))
      (node (ref "IC3") (pin "58") (pinfunction "VSSQ_58") (pintype "input"))
      (node (ref "IC3") (pin "6") (pinfunction "VSSQ_6") (pintype "input"))
      (node (ref "IC3") (pin "64") (pinfunction "VSSQ_64") (pintype "input"))
      (node (ref "IC3") (pin "66") (pinfunction "VSS_66") (pintype "input"))
      (node (ref "JP1") (pin "GND") (pinfunction "GND_GND") (pintype "bidirectional"))
      (node (ref "LDONE") (pin "C") (pinfunction "C_C") (pintype "passive"))
      (node (ref "LPWR") (pin "C") (pinfunction "C_C") (pintype "passive"))
      (node (ref "R18") (pin "1") (pinfunction "1_1") (pintype "passive"))
      (node (ref "R20") (pin "1") (pinfunction "1_1") (pintype "passive"))
      (node (ref "R22") (pin "2") (pinfunction "2_2") (pintype "passive"))
      (node (ref "R23") (pin "2") (pinfunction "2_2") (pintype "passive"))
      (node (ref "R33") (pin "2") (pinfunction "2_2") (pintype "passive"))
      (node (ref "R34") (pin "1") (pinfunction "1_1") (pintype "passive"))
      (node (ref "R35") (pin "1") (pinfunction "1_1") (pintype "passive"))
      (node (ref "R37") (pin "1") (pinfunction "1_1") (pintype "passive"))
      (node (ref "R40") (pin "1") (pinfunction "1_1") (pintype "passive"))
      (node (ref "R41") (pin "1") (pinfunction "1_1") (pintype "passive"))
      (node (ref "R44") (pin "1") (pinfunction "1_1") (pintype "passive"))
      (node (ref "R45") (pin "2") (pinfunction "2_2") (pintype "passive"))
      (node (ref "R47") (pin "1") (pinfunction "1_1") (pintype "passive"))
      (node (ref "S1") (pin "3") (pinfunction "3_3") (pintype "passive"))
      (node (ref "SB5") (pin "R1") (pinfunction "P$2_R1") (pintype "passive"))
      (node (ref "U$10") (pin "4") (pinfunction "GND_4") (pintype "bidirectional"))
      (node (ref "U$11") (pin "1") (pinfunction "GND_1") (pintype "input"))
      (node (ref "U$13") (pin "1") (pinfunction "GND_1") (pintype "input"))
      (node (ref "U$14") (pin "1") (pinfunction "GND_1") (pintype "input"))
      (node (ref "U$20") (pin "25") (pinfunction "GND_25") (pintype "input"))
      (node (ref "U$20") (pin "26") (pinfunction "GND_26") (pintype "input"))
      (node (ref "U$20") (pin "27") (pinfunction "GND_27") (pintype "input"))
      (node (ref "U$20") (pin "28") (pinfunction "GND_28") (pintype "input"))
      (node (ref "U$20") (pin "29") (pinfunction "GND_29") (pintype "input"))
      (node (ref "U$20") (pin "30") (pinfunction "GND_30") (pintype "input"))
      (node (ref "U$20") (pin "31") (pinfunction "GND_31") (pintype "input"))
      (node (ref "U$20") (pin "32") (pinfunction "GND_32") (pintype "input"))
      (node (ref "U$20") (pin "33") (pinfunction "GND_33") (pintype "input"))
      (node (ref "U$20") (pin "34") (pinfunction "GND_34") (pintype "input"))
      (node (ref "U$3") (pin "A10") (pinfunction "C0_A10") (pintype "bidirectional"))
      (node (ref "U$3") (pin "A11") (pinfunction "C1_A11") (pintype "bidirectional"))
      (node (ref "U$3") (pin "A14") (pinfunction "E2_A14") (pintype "bidirectional"))
      (node (ref "U$3") (pin "A3") (pinfunction "DSEN_A3") (pintype "bidirectional"))
      (node (ref "U$3") (pin "A4") (pinfunction "GND_A4") (pintype "input"))
      (node (ref "U$3") (pin "A9") (pinfunction "E0_A9") (pintype "bidirectional"))
      (node (ref "U$3") (pin "B10") (pinfunction "D0_B10") (pintype "bidirectional"))
      (node (ref "U$3") (pin "B11") (pinfunction "D1_B11") (pintype "bidirectional"))
      (node (ref "U$3") (pin "B14") (pinfunction "E3_B14") (pintype "bidirectional"))
      (node (ref "U$3") (pin "B3") (pinfunction "MSEN_B3") (pintype "bidirectional"))
      (node (ref "U$3") (pin "B4") (pinfunction "GND_B4") (pintype "input"))
      (node (ref "U$3") (pin "B9") (pinfunction "E1_B9") (pintype "bidirectional"))
      (node (ref "U$6") (pin "2") (pinfunction "GND_2") (pintype "bidirectional"))
      (node (ref "X2") (pin "10") (pinfunction "10_10") (pintype "passive"))
      (node (ref "X2") (pin "5") (pinfunction "5_5") (pintype "passive"))
      (node (ref "X2") (pin "6") (pinfunction "6_6") (pintype "passive"))
      (node (ref "X2") (pin "7") (pinfunction "7_7") (pintype "passive"))
      (node (ref "X2") (pin "8") (pinfunction "8_8") (pintype "passive"))
    )
    (net (code "160") (name "Net-(C56-Pad1)") (class "Default")
      (node (ref "C56") (pin "1") (pinfunction "1_1") (pintype "passive"))
      (node (ref "CONN7") (pin "P") (pinfunction "P_P") (pintype "bidirectional"))
      (node (ref "JP1") (pin "VBUS") (pinfunction "VBUS_VBUS") (pintype "bidirectional"))
      (node (ref "R43") (pin "2") (pinfunction "2_2") (pintype "passive"))
    )
    (net (code "161") (name "Net-(C57-Pad2)") (class "Default")
      (node (ref "C57") (pin "2") (pinfunction "2_2") (pintype "passive"))
      (node (ref "JP1") (pin "MT1") (pinfunction "SHELL_MT1") (pintype "bidirectional"))
      (node (ref "JP1") (pin "MT2") (pinfunction "SHELL_MT2") (pintype "bidirectional"))
      (node (ref "JP1") (pin "P$1") (pinfunction "SHELL_P$1") (pintype "bidirectional"))
      (node (ref "JP1") (pin "P$2") (pinfunction "SHELL_P$2") (pintype "bidirectional"))
      (node (ref "R47") (pin "2") (pinfunction "2_2") (pintype "passive"))
    )
    (net (code "162") (name "Net-(DDR3_0-CS#)") (class "Default")
      (node (ref "DDR3_0") (pin "L2") (pinfunction "CS#_L2") (pintype "input"))
      (node (ref "R20") (pin "2") (pinfunction "2_2") (pintype "passive"))
    )
    (net (code "163") (name "Net-(DDR3_0-ZQ)") (class "Default")
      (node (ref "DDR3_0") (pin "L8") (pinfunction "ZQ_L8") (pintype "bidirectional"))
      (node (ref "R23") (pin "1") (pinfunction "1_1") (pintype "passive"))
    )
    (net (code "164") (name "Net-(IC1-IO_L1N_VREF_0)") (class "Default")
      (node (ref "IC1") (pin "A4") (pinfunction "IO_L1N_VREF_0_A4") (pintype "bidirectional"))
      (node (ref "IC1") (pin "A5") (pinfunction "IO_L2N_0_A5") (pintype "bidirectional"))
    )
    (net (code "165") (name "Net-(IC1-IO_L1P_3)") (class "Default")
      (node (ref "IC1") (pin "M4") (pinfunction "IO_L1P_3_M4") (pintype "bidirectional"))
      (node (ref "R33") (pin "1") (pinfunction "1_1") (pintype "passive"))
    )
    (net (code "166") (name "Net-(IC1-IO_L1P_A25_1)") (class "Default")
      (node (ref "IC1") (pin "E13") (pinfunction "IO_L1P_A25_1_E13") (pintype "bidirectional"))
      (node (ref "R22") (pin "1") (pinfunction "1_1") (pintype "passive"))
    )
    (net (code "167") (name "Net-(IC1-IO_L2P_0)") (class "Default")
      (node (ref "IC1") (pin "B5") (pinfunction "IO_L2P_0_B5") (pintype "bidirectional"))
      (node (ref "IC1") (pin "B6") (pinfunction "IO_L4P_0_B6") (pintype "bidirectional"))
    )
    (net (code "168") (name "Net-(IC1-IO_L3N_0)") (class "Default")
      (node (ref "IC1") (pin "C5") (pinfunction "IO_L3N_0_C5") (pintype "bidirectional"))
      (node (ref "IC1") (pin "D5") (pinfunction "IO_L3P_0_D5") (pintype "bidirectional"))
    )
    (net (code "169") (name "Net-(IC1-IO_L7N_0)") (class "Default")
      (node (ref "IC1") (pin "C6") (pinfunction "IO_L7N_0_C6") (pintype "bidirectional"))
      (node (ref "IC1") (pin "D6") (pinfunction "IO_L7P_0_D6") (pintype "bidirectional"))
    )
    (net (code "170") (name "Net-(IC1-IO_L33P_0)") (class "Default")
      (node (ref "IC1") (pin "B8") (pinfunction "IO_L33P_0_B8") (pintype "bidirectional"))
      (node (ref "IC1") (pin "C9") (pinfunction "IO_L34P_GCLK19_0_C9") (pintype "bidirectional"))
    )
    (net (code "171") (name "Net-(IC1-IO_L36N_GCLK14_0)") (class "Default")
      (node (ref "IC1") (pin "D8") (pinfunction "IO_L38P_0_D8") (pintype "bidirectional"))
      (node (ref "IC1") (pin "E8") (pinfunction "IO_L36N_GCLK14_0_E8") (pintype "bidirectional"))
    )
    (net (code "172") (name "Net-(IC1-IO_L36P_GCLK15_0)") (class "Default")
      (node (ref "IC1") (pin "E6") (pinfunction "IO_L5N_0_E6") (pintype "bidirectional"))
      (node (ref "IC1") (pin "E7") (pinfunction "IO_L36P_GCLK15_0_E7") (pintype "bidirectional"))
    )
    (net (code "173") (name "Net-(IC1-IO_L37N_GCLK12_0)") (class "Default")
      (node (ref "IC1") (pin "C10") (pinfunction "IO_L37N_GCLK12_0_C10") (pintype "bidirectional"))
      (node (ref "IC1") (pin "D9") (pinfunction "IO_L40N_0_D9") (pintype "bidirectional"))
    )
    (net (code "174") (name "Net-(IC1-IO_L38N_VREF_0)") (class "Default")
      (node (ref "IC1") (pin "C7") (pinfunction "IO_L6P_0_C7") (pintype "bidirectional"))
      (node (ref "IC1") (pin "C8") (pinfunction "IO_L38N_VREF_0_C8") (pintype "bidirectional"))
    )
    (net (code "175") (name "Net-(IC1-IO_L64N_SCP4_0)") (class "Default")
      (node (ref "IC1") (pin "D11") (pinfunction "IO_L66P_SCP1_0_D11") (pintype "bidirectional"))
      (node (ref "IC1") (pin "E11") (pinfunction "IO_L64N_SCP4_0_E11") (pintype "bidirectional"))
    )
    (net (code "176") (name "Net-(IC1-IO_L65P_INIT_B_2)") (class "Default")
      (node (ref "IC1") (pin "R3") (pinfunction "IO_L65P_INIT_B_2_R3") (pintype "bidirectional"))
      (node (ref "R32") (pin "1") (pinfunction "1_1") (pintype "passive"))
    )
    (net (code "177") (name "Net-(IC3-CS#)") (class "Default")
      (node (ref "IC3") (pin "24") (pinfunction "CS#_24") (pintype "input"))
      (node (ref "R34") (pin "2") (pinfunction "2_2") (pintype "passive"))
    )
    (net (code "178") (name "Net-(L0-PadC)") (class "Default")
      (node (ref "L0") (pin "C") (pinfunction "C_C") (pintype "passive"))
      (node (ref "R19") (pin "2") (pinfunction "2_2") (pintype "passive"))
    )
    (net (code "179") (name "Net-(L1-PadC)") (class "Default")
      (node (ref "L1") (pin "C") (pinfunction "C_C") (pintype "passive"))
      (node (ref "R24") (pin "2") (pinfunction "2_2") (pintype "passive"))
    )
    (net (code "180") (name "Net-(L2-PadC)") (class "Default")
      (node (ref "L2") (pin "C") (pinfunction "C_C") (pintype "passive"))
      (node (ref "R25") (pin "2") (pinfunction "2_2") (pintype "passive"))
    )
    (net (code "181") (name "Net-(LDONE-PadA)") (class "Default")
      (node (ref "LDONE") (pin "A") (pinfunction "A_A") (pintype "passive"))
      (node (ref "R38") (pin "1") (pinfunction "1_1") (pintype "passive"))
    )
    (net (code "182") (name "Net-(LPWR-PadA)") (class "Default")
      (node (ref "LPWR") (pin "A") (pinfunction "A_A") (pintype "passive"))
      (node (ref "R30") (pin "1") (pinfunction "1_1") (pintype "passive"))
    )
    (net (code "183") (name "Net-(R1-Pad1)") (class "Default")
      (node (ref "R1") (pin "1") (pinfunction "1_1") (pintype "passive"))
      (node (ref "X2") (pin "14") (pinfunction "14_14") (pintype "passive"))
    )
    (net (code "184") (name "Net-(R2-Pad1)") (class "Default")
      (node (ref "R2") (pin "1") (pinfunction "1_1") (pintype "passive"))
      (node (ref "X2") (pin "13") (pinfunction "13_13") (pintype "passive"))
    )
    (net (code "185") (name "Net-(R10-Pad2)") (class "Default")
      (node (ref "R10") (pin "2") (pinfunction "2_2") (pintype "passive"))
      (node (ref "R13") (pin "2") (pinfunction "2_2") (pintype "passive"))
      (node (ref "R16") (pin "2") (pinfunction "2_2") (pintype "passive"))
      (node (ref "R4") (pin "2") (pinfunction "2_2") (pintype "passive"))
      (node (ref "R7") (pin "2") (pinfunction "2_2") (pintype "passive"))
      (node (ref "X2") (pin "2") (pinfunction "2_2") (pintype "passive"))
    )
    (net (code "186") (name "Net-(R11-Pad2)") (class "Default")
      (node (ref "R11") (pin "2") (pinfunction "2_2") (pintype "passive"))
      (node (ref "R14") (pin "2") (pinfunction "2_2") (pintype "passive"))
      (node (ref "R17") (pin "2") (pinfunction "2_2") (pintype "passive"))
      (node (ref "R5") (pin "2") (pinfunction "2_2") (pintype "passive"))
      (node (ref "R8") (pin "2") (pinfunction "2_2") (pintype "passive"))
      (node (ref "X2") (pin "1") (pinfunction "1_1") (pintype "passive"))
    )
    (net (code "187") (name "Net-(R12-Pad2)") (class "Default")
      (node (ref "R12") (pin "2") (pinfunction "2_2") (pintype "passive"))
      (node (ref "R15") (pin "2") (pinfunction "2_2") (pintype "passive"))
      (node (ref "R3") (pin "2") (pinfunction "2_2") (pintype "passive"))
      (node (ref "R6") (pin "2") (pinfunction "2_2") (pintype "passive"))
      (node (ref "R9") (pin "2") (pinfunction "2_2") (pintype "passive"))
      (node (ref "X2") (pin "3") (pinfunction "3_3") (pintype "passive"))
    )
    (net (code "188") (name "Net-(SB2-P$2)") (class "Default")
      (node (ref "R48") (pin "1") (pinfunction "1_1") (pintype "passive"))
      (node (ref "SB1") (pin "R1") (pinfunction "P$2_R1") (pintype "passive"))
      (node (ref "SB1") (pin "R2") (pinfunction "P$2_R2") (pintype "passive"))
      (node (ref "SB2") (pin "R1") (pinfunction "P$2_R1") (pintype "passive"))
    )
    (net (code "189") (name "Net-(U$3-3.3V)") (class "Default")
      (node (ref "R46") (pin "1") (pinfunction "1_1") (pintype "passive"))
      (node (ref "U$3") (pin "A7") (pinfunction "3.3V_A7") (pintype "bidirectional"))
    )
    (net (code "190") (name "Net-(U$20-DM)") (class "Default")
      (node (ref "JP1") (pin "D-") (pinfunction "D-_D-") (pintype "bidirectional"))
      (node (ref "U$20") (pin "14") (pinfunction "DM_14") (pintype "bidirectional"))
    )
    (net (code "191") (name "Net-(U$20-DP)") (class "Default")
      (node (ref "JP1") (pin "D+") (pinfunction "D+_D+") (pintype "bidirectional"))
      (node (ref "U$20") (pin "13") (pinfunction "DP_13") (pintype "bidirectional"))
    )
    (net (code "192") (name "Net-(U$20-ID)") (class "Default")
      (node (ref "JP1") (pin "ID") (pinfunction "ID_ID") (pintype "bidirectional"))
      (node (ref "U$20") (pin "18") (pinfunction "ID_18") (pintype "input"))
    )
    (net (code "193") (name "Net-(U$20-RBIAS)") (class "Default")
      (node (ref "R45") (pin "1") (pinfunction "1_1") (pintype "passive"))
      (node (ref "U$20") (pin "19") (pinfunction "RBIAS_19") (pintype "output"))
    )
    (net (code "194") (name "Net-(U$20-VBUS)") (class "Default")
      (node (ref "R43") (pin "1") (pinfunction "1_1") (pintype "passive"))
      (node (ref "U$20") (pin "17") (pinfunction "VBUS_17") (pintype "input"))
    )
    (net (code "195") (name "Net-(U$20-VDD18)") (class "Default")
      (node (ref "C53") (pin "1") (pinfunction "1_1") (pintype "passive"))
      (node (ref "U$20") (pin "23") (pinfunction "VDD18_23") (pintype "output"))
    )
    (net (code "196") (name "Net-(U$20-VDD33)") (class "Default")
      (node (ref "C55") (pin "1") (pinfunction "1_1") (pintype "passive"))
      (node (ref "U$20") (pin "15") (pinfunction "VDD33_15") (pintype "output"))
    )
    (net (code "197") (name "unconnected-(IC1-CMPCS_B_2-PadL11)") (class "Default")
      (node (ref "IC1") (pin "L11") (pinfunction "CMPCS_B_2_L11") (pintype "bidirectional"))
    )
    (net (code "198") (name "unconnected-(IC1-IO_L2N_3-PadN4)") (class "Default")
      (node (ref "IC1") (pin "N4") (pinfunction "IO_L2N_3_N4") (pintype "bidirectional"))
    )
    (net (code "199") (name "unconnected-(IC1-IO_L2P_3-PadM5)") (class "Default")
      (node (ref "IC1") (pin "M5") (pinfunction "IO_L2P_3_M5") (pintype "bidirectional"))
    )
    (net (code "200") (name "unconnected-(IC1-IO_L5P_0-PadF7)") (class "Default")
      (node (ref "IC1") (pin "F7") (pinfunction "IO_L5P_0_F7") (pintype "bidirectional"))
    )
    (net (code "201") (name "unconnected-(IC1-IO_L29N_A22_M1A14_1-PadB16)") (class "Default")
      (node (ref "IC1") (pin "B16") (pinfunction "IO_L29N_A22_M1A14_1_B16") (pintype "bidirectional"))
    )
    (net (code "202") (name "unconnected-(IC1-IO_L29P_A23_M1A13_1-PadB15)") (class "Default")
      (node (ref "IC1") (pin "B15") (pinfunction "IO_L29P_A23_M1A13_1_B15") (pintype "bidirectional"))
    )
    (net (code "203") (name "unconnected-(IC1-IO_L30P_A21_M1RESET_1-PadF12)") (class "Default")
      (node (ref "IC1") (pin "F12") (pinfunction "IO_L30P_A21_M1RESET_1_F12") (pintype "bidirectional"))
    )
    (net (code "204") (name "unconnected-(IC1-IO_L34N_A12_M1BA2_1-PadE16)") (class "Default")
      (node (ref "IC1") (pin "E16") (pinfunction "IO_L34N_A12_M1BA2_1_E16") (pintype "bidirectional"))
    )
    (net (code "205") (name "unconnected-(IC1-IO_L39N_M1ODT_1-PadH14)") (class "Default")
      (node (ref "IC1") (pin "H14") (pinfunction "IO_L39N_M1ODT_1_H14") (pintype "bidirectional"))
    )
    (net (code "206") (name "unconnected-(IC1-IO_L40P_0-PadF9)") (class "Default")
      (node (ref "IC1") (pin "F9") (pinfunction "IO_L40P_0_F9") (pintype "bidirectional"))
    )
    (net (code "207") (name "unconnected-(IC1-IO_L45N_A0_M1LDQSN_1-PadN16)") (class "Default")
      (node (ref "IC1") (pin "N16") (pinfunction "IO_L45N_A0_M1LDQSN_1_N16") (pintype "bidirectional"))
    )
    (net (code "208") (name "unconnected-(IC1-IO_L50N_M1UDQSN_1-PadT15)") (class "Default")
      (node (ref "IC1") (pin "T15") (pinfunction "IO_L50N_M1UDQSN_1_T15") (pintype "bidirectional"))
    )
    (net (code "209") (name "unconnected-(IC1-IO_L53P_1-PadL12)") (class "Default")
      (node (ref "IC1") (pin "L12") (pinfunction "IO_L53P_1_L12") (pintype "bidirectional"))
    )
    (net (code "210") (name "unconnected-(IC1-IO_L64P_SCP5_0-PadF10)") (class "Default")
      (node (ref "IC1") (pin "F10") (pinfunction "IO_L64P_SCP5_0_F10") (pintype "bidirectional"))
    )
    (net (code "211") (name "unconnected-(IC1-IO_L74N_DOUT_BUSY_1-PadM14)") (class "Default")
      (node (ref "IC1") (pin "M14") (pinfunction "IO_L74N_DOUT_BUSY_1_M14") (pintype "bidirectional"))
    )
    (net (code "212") (name "unconnected-(IC1-IO_L74P_AWAKE_1-PadM13)") (class "Default")
      (node (ref "IC1") (pin "M13") (pinfunction "IO_L74P_AWAKE_1_M13") (pintype "bidirectional"))
    )
    (net (code "213") (name "unconnected-(IC1-IO_L83P_3-PadB3)") (class "Default")
      (node (ref "IC1") (pin "B3") (pinfunction "IO_L83P_3_B3") (pintype "bidirectional"))
    )
    (net (code "214") (name "unconnected-(S1-Pad1)") (class "Default")
      (node (ref "S1") (pin "1") (pinfunction "1_1") (pintype "passive"))
    )
    (net (code "215") (name "unconnected-(S1-Pad4)") (class "Default")
      (node (ref "S1") (pin "4") (pinfunction "4_4") (pintype "passive"))
    )
    (net (code "216") (name "unconnected-(U$3-1.8V-PadB7)") (class "Default")
      (node (ref "U$3") (pin "B7") (pinfunction "1.8V_B7") (pintype "bidirectional"))
    )
    (net (code "217") (name "unconnected-(U$3-12V-PadA8)") (class "Default")
      (node (ref "U$3") (pin "A8") (pinfunction "12V_A8") (pintype "bidirectional"))
    )
    (net (code "218") (name "unconnected-(U$3-12V-PadB8)") (class "Default")
      (node (ref "U$3") (pin "B8") (pinfunction "12V_B8") (pintype "bidirectional"))
    )
    (net (code "219") (name "unconnected-(U$3-G0-PadB6)") (class "Default")
      (node (ref "U$3") (pin "B6") (pinfunction "G0_B6") (pintype "bidirectional"))
    )
    (net (code "220") (name "unconnected-(U$3-SCL-PadA5)") (class "Default")
      (node (ref "U$3") (pin "A5") (pinfunction "SCL_A5") (pintype "bidirectional"))
    )
    (net (code "221") (name "unconnected-(U$3-SDA-PadA6)") (class "Default")
      (node (ref "U$3") (pin "A6") (pinfunction "SDA_A6") (pintype "bidirectional"))
    )
    (net (code "222") (name "unconnected-(U$20-XO-Pad20)") (class "Default")
      (node (ref "U$20") (pin "20") (pinfunction "XO_20") (pintype "bidirectional"))
    )
    (net (code "223") (name "unconnected-(X2-Pad4)") (class "Default")
      (node (ref "X2") (pin "4") (pinfunction "4_4") (pintype "passive"))
    )
    (net (code "224") (name "unconnected-(X2-Pad9)") (class "Default")
      (node (ref "X2") (pin "9") (pinfunction "9_9") (pintype "passive"))
    )
    (net (code "225") (name "unconnected-(X2-Pad11)") (class "Default")
      (node (ref "X2") (pin "11") (pinfunction "11_11") (pintype "passive"))
    )
    (net (code "226") (name "unconnected-(X2-Pad12)") (class "Default")
      (node (ref "X2") (pin "12") (pinfunction "12_12") (pintype "passive"))
    )
    (net (code "227") (name "unconnected-(X2-Pad15)") (class "Default")
      (node (ref "X2") (pin "15") (pinfunction "15_15") (pintype "passive"))
    )
  )
)
